# STM32F767IGT6.net
KiCad netlist of a schematic drawn in Altium Designer
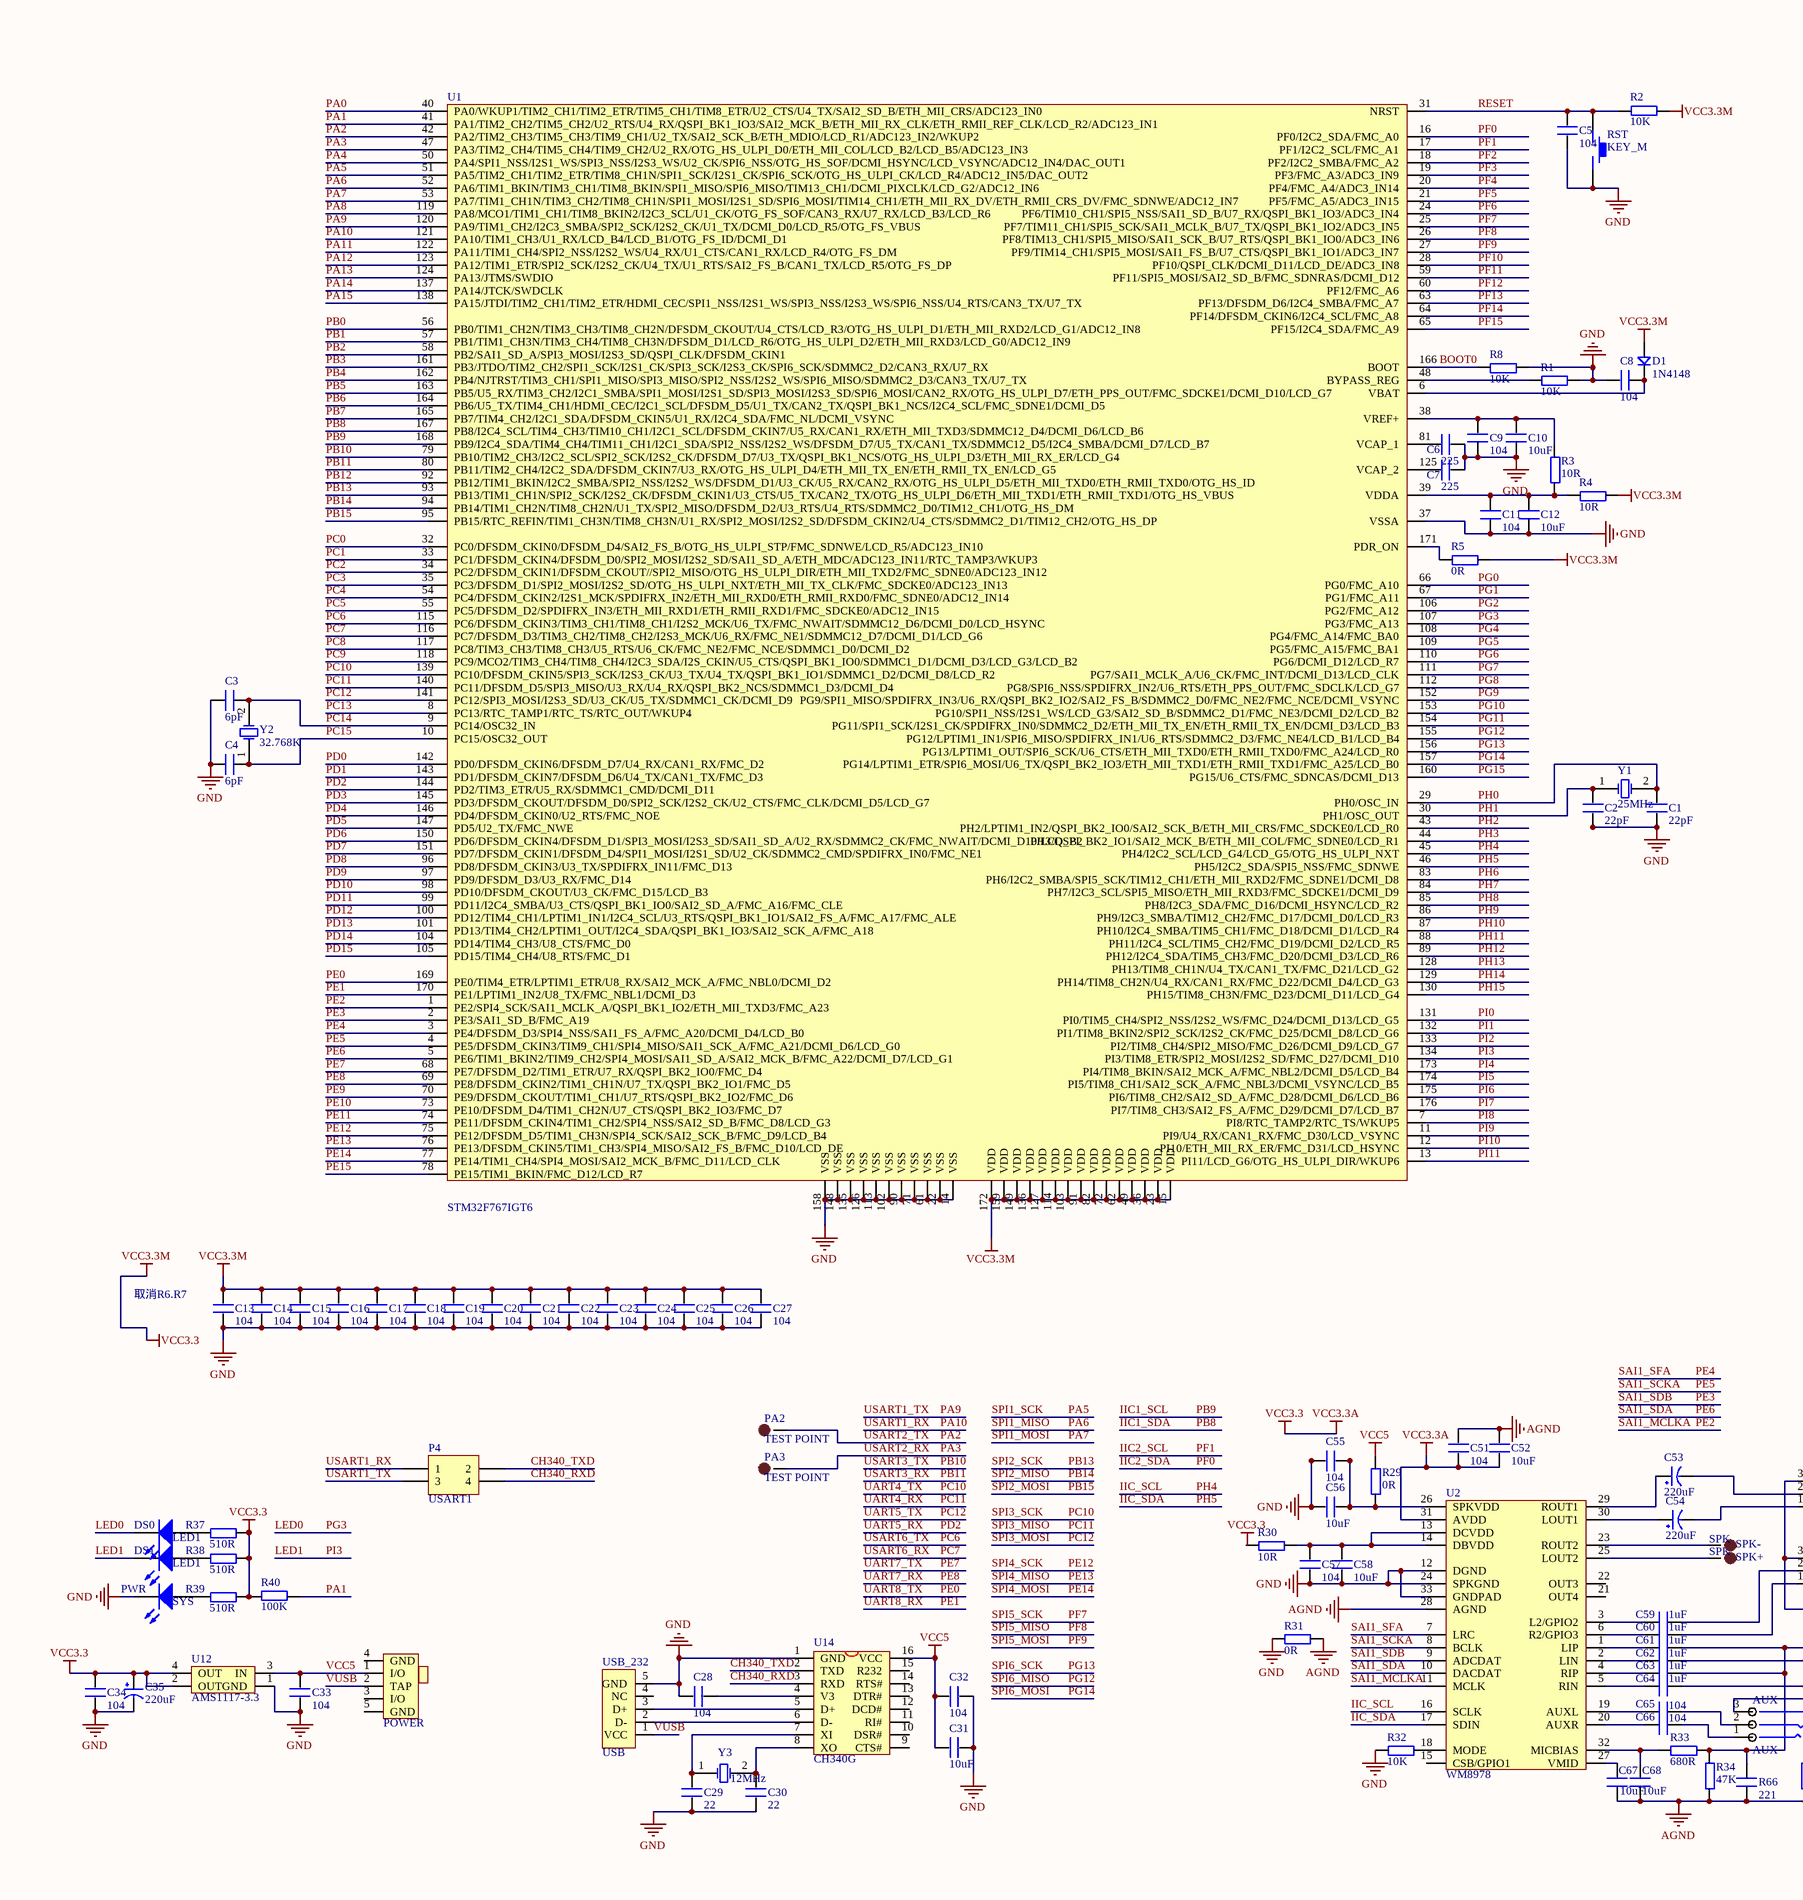
[diagram p0: STM32F767IGT6.SchDoc, left]
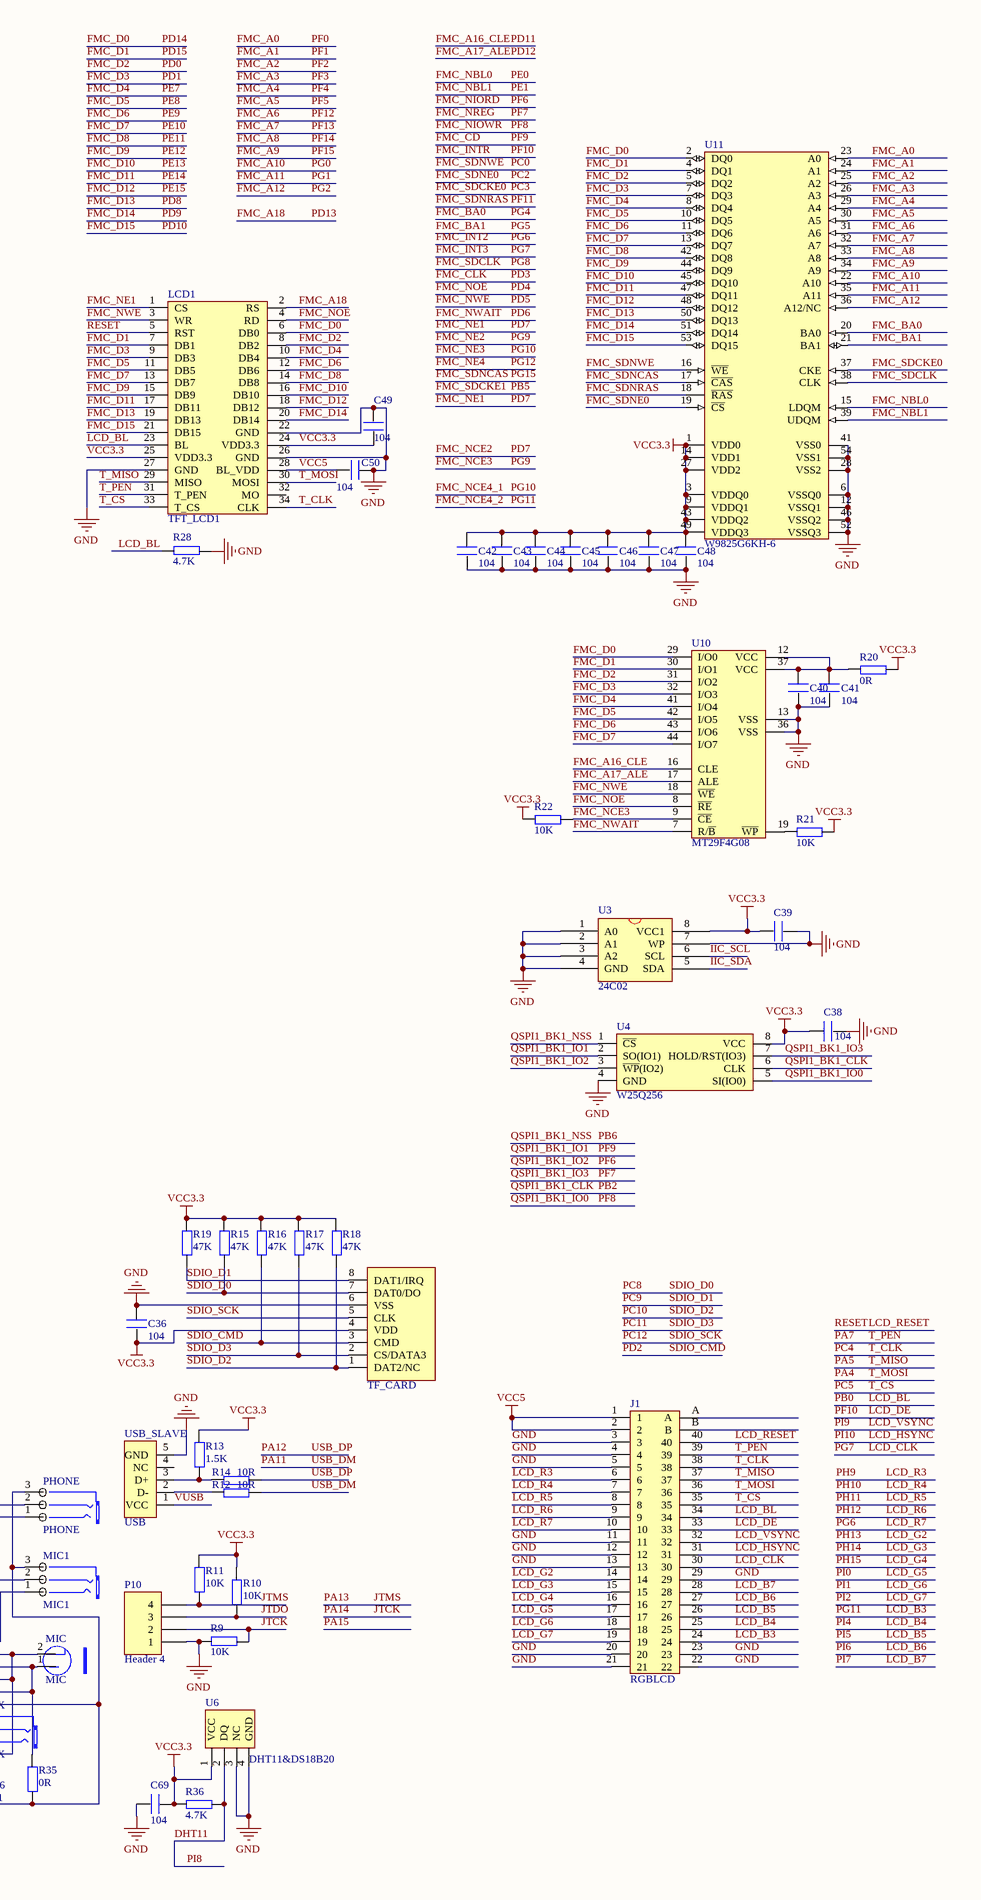
[diagram p1: STM32F767IGT6.SchDoc, right]

(export (version "E")
  (design (tool "Eeschema 10.0.6"))
  (components
    (comp (ref "AUX")
      (value "AUX")
      (footprint "PHONE_ST")
      (libsource (lib "阿波罗STM32F4&F7&H7底板封装库") (part "PHONE_M"))
    )
    (comp (ref "C1")
      (value "22pF")
      (footprint "C 0603_M")
      (libsource (lib "WarShip V3 STM32103封装库") (part "C"))
    )
    (comp (ref "C2")
      (value "22pF")
      (footprint "C 0603_M")
      (libsource (lib "WarShip V3 STM32103封装库") (part "C"))
    )
    (comp (ref "C3")
      (value "6pF")
      (footprint "C 0603_M")
      (libsource (lib "WarShip V3 STM32103封装库") (part "C"))
    )
    (comp (ref "C4")
      (value "6pF")
      (footprint "C 0603_M")
      (libsource (lib "WarShip V3 STM32103封装库") (part "C"))
    )
    (comp (ref "C5")
      (value "104")
      (footprint "C 0603_M")
      (libsource (lib "WarShip V3 STM32103封装库") (part "C"))
    )
    (comp (ref "C6") (value "225") (footprint "C 0603_M") (libsource (lib "阿波罗STM32F4&F7底板封装库") (part "C")))
    (comp (ref "C7") (value "225") (footprint "C 0603_M") (libsource (lib "阿波罗STM32F4&F7底板封装库") (part "C")))
    (comp (ref "C8") (value "104") (footprint "C 0603_M") (libsource (lib "阿波罗STM32F4&F7底板封装库") (part "C")))
    (comp (ref "C9") (value "104") (footprint "C 0603_M") (libsource (lib "阿波罗STM32F4&F7底板封装库") (part "C")))
    (comp (ref "C10") (value "10uF") (footprint "C 0603_M") (libsource (lib "阿波罗STM32F4&F7底板封装库") (part "C")))
    (comp (ref "C11") (value "104") (footprint "C 0603_M") (libsource (lib "阿波罗STM32F4&F7底板封装库") (part "C")))
    (comp (ref "C12") (value "10uF") (footprint "C 0603_M") (libsource (lib "阿波罗STM32F4&F7底板封装库") (part "C")))
    (comp (ref "C13") (value "104") (footprint "C 0603_M") (libsource (lib "STM32F429核心板封装库") (part "C")))
    (comp (ref "C14") (value "104") (footprint "C 0603_M") (libsource (lib "STM32F429核心板封装库") (part "C")))
    (comp (ref "C15") (value "104") (footprint "C 0603_M") (libsource (lib "STM32F429核心板封装库") (part "C")))
    (comp (ref "C16") (value "104") (footprint "C 0603_M") (libsource (lib "STM32F429核心板封装库") (part "C")))
    (comp (ref "C17") (value "104") (footprint "C 0603_M") (libsource (lib "STM32F429核心板封装库") (part "C")))
    (comp (ref "C18") (value "104") (footprint "C 0603_M") (libsource (lib "STM32F429核心板封装库") (part "C")))
    (comp (ref "C19") (value "104") (footprint "C 0603_M") (libsource (lib "STM32F429核心板封装库") (part "C")))
    (comp (ref "C20") (value "104") (footprint "C 0603_M") (libsource (lib "STM32F429核心板封装库") (part "C")))
    (comp (ref "C21") (value "104") (footprint "C 0603_M") (libsource (lib "STM32F429核心板封装库") (part "C")))
    (comp (ref "C22") (value "104") (footprint "C 0603_M") (libsource (lib "STM32F429核心板封装库") (part "C")))
    (comp (ref "C23") (value "104") (footprint "C 0603_M") (libsource (lib "STM32F429核心板封装库") (part "C")))
    (comp (ref "C24") (value "104") (footprint "C 0603_M") (libsource (lib "STM32F429核心板封装库") (part "C")))
    (comp (ref "C25") (value "104") (footprint "C 0603_M") (libsource (lib "STM32F429核心板封装库") (part "C")))
    (comp (ref "C26") (value "104") (footprint "C 0603_M") (libsource (lib "STM32F429核心板封装库") (part "C")))
    (comp (ref "C27") (value "104") (footprint "C 0603_M") (libsource (lib "STM32F429核心板封装库") (part "C")))
    (comp (ref "C28")
      (value "104")
      (footprint "C 0603_M")
      (libsource (lib "WarShip V3 STM32103封装库") (part "C"))
    )
    (comp (ref "C29")
      (value "22")
      (footprint "C 0603_M")
      (libsource (lib "WarShip V3 STM32103封装库") (part "C"))
    )
    (comp (ref "C30")
      (value "22")
      (footprint "C 0603_M")
      (libsource (lib "WarShip V3 STM32103封装库") (part "C"))
    )
    (comp (ref "C31")
      (value "10uF")
      (footprint "C 0603_M")
      (libsource (lib "WarShip V3 STM32103封装库") (part "C"))
    )
    (comp (ref "C32")
      (value "104")
      (footprint "C 0603_M")
      (libsource (lib "WarShip V3 STM32103封装库") (part "C"))
    )
    (comp (ref "C33")
      (value "104")
      (footprint "C 0603_M")
      (libsource (lib "WarShip V3 STM32103封装库") (part "C"))
    )
    (comp (ref "C34")
      (value "104")
      (footprint "C 0603_M")
      (libsource (lib "WarShip V3 STM32103封装库") (part "C"))
    )
    (comp (ref "C35")
      (value "220uF")
      (footprint "CT 6*6 - C")
      (libsource (lib "WarShip V3 STM32103封装库") (part "CAP"))
    )
    (comp (ref "C36")
      (value "104")
      (footprint "C 0603_M")
      (libsource (lib "WarShip V3 STM32103封装库") (part "C"))
    )
    (comp (ref "C38")
      (value "104")
      (footprint "C 0603_M")
      (libsource (lib "WarShip V3 STM32103封装库") (part "C"))
    )
    (comp (ref "C39")
      (value "104")
      (footprint "C 0603_M")
      (libsource (lib "WarShip V3 STM32103封装库") (part "C"))
    )
    (comp (ref "C40")
      (value "104")
      (footprint "C 0603_M")
      (libsource (lib "WarShip V3 STM32103封装库") (part "C"))
    )
    (comp (ref "C41")
      (value "104")
      (footprint "C 0603_M")
      (libsource (lib "WarShip V3 STM32103封装库") (part "C"))
    )
    (comp (ref "C42")
      (value "104")
      (footprint "C 0603_M")
      (libsource (lib "WarShip V3 STM32103封装库") (part "C"))
    )
    (comp (ref "C43")
      (value "104")
      (footprint "C 0603_M")
      (libsource (lib "WarShip V3 STM32103封装库") (part "C"))
    )
    (comp (ref "C44")
      (value "104")
      (footprint "C 0603_M")
      (libsource (lib "WarShip V3 STM32103封装库") (part "C"))
    )
    (comp (ref "C45")
      (value "104")
      (footprint "C 0603_M")
      (libsource (lib "WarShip V3 STM32103封装库") (part "C"))
    )
    (comp (ref "C46")
      (value "104")
      (footprint "C 0603_M")
      (libsource (lib "WarShip V3 STM32103封装库") (part "C"))
    )
    (comp (ref "C47")
      (value "104")
      (footprint "C 0603_M")
      (libsource (lib "WarShip V3 STM32103封装库") (part "C"))
    )
    (comp (ref "C48")
      (value "104")
      (footprint "C 0603_M")
      (libsource (lib "WarShip V3 STM32103封装库") (part "C"))
    )
    (comp (ref "C49") (value "104") (footprint "C 0603_M") (libsource (lib "MYCOMLIB") (part "C")))
    (comp (ref "C50") (value "104") (footprint "C 0603_M") (libsource (lib "MYCOMLIB") (part "C")))
    (comp (ref "C51") (value "104") (footprint "C 0603_M") (libsource (lib "阿波罗STM32F4&F7底板封装库") (part "C")))
    (comp (ref "C52") (value "10uF") (footprint "C 0603_M") (libsource (lib "阿波罗STM32F4&F7底板封装库") (part "C")))
    (comp (ref "C53")
      (value "220uF")
      (footprint "cc4*5.4")
      (libsource (lib "阿波罗STM32F4&F7底板封装库") (part "CAP"))
    )
    (comp (ref "C54")
      (value "220uF")
      (footprint "cc4*5.4")
      (libsource (lib "阿波罗STM32F4&F7底板封装库") (part "CAP"))
    )
    (comp (ref "C55") (value "104") (footprint "C 0603_M") (libsource (lib "阿波罗STM32F4&F7底板封装库") (part "C")))
    (comp (ref "C56") (value "10uF") (footprint "C 0603_M") (libsource (lib "阿波罗STM32F4&F7底板封装库") (part "C")))
    (comp (ref "C57") (value "104") (footprint "C 0603_M") (libsource (lib "阿波罗STM32F4&F7底板封装库") (part "C")))
    (comp (ref "C58") (value "10uF") (footprint "C 0603_M") (libsource (lib "阿波罗STM32F4&F7底板封装库") (part "C")))
    (comp (ref "C59") (value "1uF") (footprint "C 0603_M") (libsource (lib "阿波罗STM32F4&F7底板封装库") (part "C")))
    (comp (ref "C60") (value "1uF") (footprint "C 0603_M") (libsource (lib "阿波罗STM32F4&F7底板封装库") (part "C")))
    (comp (ref "C61") (value "1uF") (footprint "C 0603_M") (libsource (lib "阿波罗STM32F4&F7底板封装库") (part "C")))
    (comp (ref "C62") (value "1uF") (footprint "C 0603_M") (libsource (lib "阿波罗STM32F4&F7底板封装库") (part "C")))
    (comp (ref "C63") (value "1uF") (footprint "C 0603_M") (libsource (lib "阿波罗STM32F4&F7底板封装库") (part "C")))
    (comp (ref "C64") (value "1uF") (footprint "C 0603_M") (libsource (lib "阿波罗STM32F4&F7底板封装库") (part "C")))
    (comp (ref "C65") (value "104") (footprint "C 0603_M") (libsource (lib "阿波罗STM32F4&F7底板封装库") (part "C")))
    (comp (ref "C66") (value "104") (footprint "C 0603_M") (libsource (lib "阿波罗STM32F4&F7底板封装库") (part "C")))
    (comp (ref "C67") (value "10uF") (footprint "C 0603_M") (libsource (lib "阿波罗STM32F4&F7底板封装库") (part "C")))
    (comp (ref "C68") (value "10uF") (footprint "C 0603_M") (libsource (lib "阿波罗STM32F4&F7底板封装库") (part "C")))
    (comp (ref "C69")
      (value "104")
      (footprint "C 0603_M")
      (libsource (lib "WarShip V3 STM32103封装库") (part "C"))
    )
    (comp (ref "D1")
      (value "1N4148")
      (footprint "DIODE_SOP")
      (libsource (lib "WarShip V3 STM32103封装库") (part "D"))
    )
    (comp (ref "DS0")
      (value "LED1")
      (footprint "SMDLED")
      (description "Typical RED, GREEN, YELLOW, AMBER GaAs LED")
      (fields (field (name "PUBLISHER") "Altium Limited"))
      (libsource (lib "Miscellaneous Devices") (part "LED2"))
    )
    (comp (ref "DS1")
      (value "LED1")
      (footprint "SMDLED")
      (description "Typical RED, GREEN, YELLOW, AMBER GaAs LED")
      (fields (field (name "PUBLISHER") "Altium Limited"))
      (libsource (lib "Miscellaneous Devices") (part "LED2"))
    )
    (comp (ref "J1")
      (value "RGBLCD")
      (footprint "FPC-TOP40")
      (description "FPC-40P-0.5mm")
      (libsource (lib "STM32F429核心板封装库") (part "FPC-40"))
    )
    (comp (ref "LCD1")
      (value "TFT_LCD1")
      (footprint "DB2*17-3.5")
      (libsource (lib "3.5TFTLCD封装库") (part "TFT_LCD2"))
    )
    (comp (ref "MIC")
      (value "MIC")
      (footprint "MIC-6022")
      (libsource (lib "阿波罗STM32F4&F7&H7底板封装库") (part "MIC"))
    )
    (comp (ref "MIC1")
      (value "MIC1")
      (footprint "PHONE_ST")
      (libsource (lib "阿波罗STM32F4&F7&H7底板封装库") (part "PHONE_M"))
    )
    (comp (ref "P4")
      (value "USART1")
      (footprint "HDR2.54-LI-2x2P")
      (description "Header, 2-Pin, Dual row")
      (fields (field (name "PUBLISHER") "Altium Limited"))
      (libsource (lib "WarShip V3 STM32103封装库") (part "Header 2X2"))
    )
    (comp (ref "P10")
      (value "Header 4")
      (footprint "HDR2.54-LI-4P")
      (description "Header, 4-Pin")
      (fields (field (name "PUBLISHER") "Altium Limited"))
      (libsource (lib "WarShip V3 STM32103封装库") (part "Header 4"))
    )
    (comp (ref "PA2")
      (value "TEST POINT")
      (footprint "TP-1.5")
      (description "测试点")
      (libsource (lib "STM32F429核心板封装库") (part "TEST-POINT"))
    )
    (comp (ref "PA3")
      (value "TEST POINT")
      (footprint "TP-1.5")
      (description "测试点")
      (libsource (lib "STM32F429核心板封装库") (part "TEST-POINT"))
    )
    (comp (ref "PHONE")
      (value "PHONE")
      (footprint "PHONE_ST")
      (libsource (lib "阿波罗STM32F4&F7&H7底板封装库") (part "PHONE_M"))
    )
    (comp (ref "POWER")
      (value "BUTTON_DIP3")
      (footprint "BTN8.8*4.6")
      (description "拨动开关SS-12F44")
      (libsource (lib "Pandora_STM32L4_Board_V2.4") (part "BUTTON_DIP3"))
    )
    (comp (ref "PWR")
      (value "SYS")
      (footprint "SMDLED")
      (description "Typical RED, GREEN, YELLOW, AMBER GaAs LED")
      (fields (field (name "PUBLISHER") "Altium Limited"))
      (libsource (lib "Miscellaneous Devices") (part "LED2"))
    )
    (comp (ref "R1") (value "10K") (footprint "R 0603_M") (libsource (lib "阿波罗STM32F4&F7底板封装库") (part "R")))
    (comp (ref "R2")
      (value "10K")
      (footprint "R 0603_M")
      (libsource (lib "WarShip V3 STM32103封装库") (part "R"))
    )
    (comp (ref "R3") (value "10R") (footprint "R 0603_M") (libsource (lib "阿波罗STM32F4&F7底板封装库") (part "R")))
    (comp (ref "R4") (value "10R") (footprint "R 0603_M") (libsource (lib "阿波罗STM32F4&F7底板封装库") (part "R")))
    (comp (ref "R5") (value "0R") (footprint "R 0603_M") (libsource (lib "阿波罗STM32F4&F7底板封装库") (part "R")))
    (comp (ref "R8") (value "10K") (footprint "R 0603_M") (libsource (lib "阿波罗STM32F4&F7底板封装库") (part "R")))
    (comp (ref "R9")
      (value "10K")
      (footprint "R 0603_M")
      (libsource (lib "WarShip V3 STM32103封装库") (part "R"))
    )
    (comp (ref "R10")
      (value "10K")
      (footprint "R 0603_M")
      (libsource (lib "WarShip V3 STM32103封装库") (part "R"))
    )
    (comp (ref "R11")
      (value "10K")
      (footprint "R 0603_M")
      (libsource (lib "WarShip V3 STM32103封装库") (part "R"))
    )
    (comp (ref "R12")
      (value "10R")
      (footprint "R 0603_M")
      (libsource (lib "WarShip V3 STM32103封装库") (part "R"))
    )
    (comp (ref "R13")
      (value "1.5K")
      (footprint "R 0603_M")
      (libsource (lib "WarShip V3 STM32103封装库") (part "R"))
    )
    (comp (ref "R14")
      (value "10R")
      (footprint "R 0603_M")
      (libsource (lib "WarShip V3 STM32103封装库") (part "R"))
    )
    (comp (ref "R15")
      (value "47K")
      (footprint "R 0603_M")
      (libsource (lib "WarShip V3 STM32103封装库") (part "R"))
    )
    (comp (ref "R16")
      (value "47K")
      (footprint "R 0603_M")
      (libsource (lib "WarShip V3 STM32103封装库") (part "R"))
    )
    (comp (ref "R17")
      (value "47K")
      (footprint "R 0603_M")
      (libsource (lib "WarShip V3 STM32103封装库") (part "R"))
    )
    (comp (ref "R18")
      (value "47K")
      (footprint "R 0603_M")
      (libsource (lib "WarShip V3 STM32103封装库") (part "R"))
    )
    (comp (ref "R19")
      (value "47K")
      (footprint "R 0603_M")
      (libsource (lib "WarShip V3 STM32103封装库") (part "R"))
    )
    (comp (ref "R20")
      (value "0R")
      (footprint "R 0603_M")
      (libsource (lib "WarShip V3 STM32103封装库") (part "R"))
    )
    (comp (ref "R21")
      (value "10K")
      (footprint "R 0603_M")
      (libsource (lib "WarShip V3 STM32103封装库") (part "R"))
    )
    (comp (ref "R22")
      (value "10K")
      (footprint "R 0603_M")
      (libsource (lib "WarShip V3 STM32103封装库") (part "R"))
    )
    (comp (ref "R28") (value "4.7K") (footprint "R 0603_M") (libsource (lib "MYCOMLIB") (part "R")))
    (comp (ref "R29") (value "0R") (footprint "R 0603_M") (libsource (lib "阿波罗STM32F4&F7底板封装库") (part "R")))
    (comp (ref "R30") (value "10R") (footprint "R 0603_M") (libsource (lib "阿波罗STM32F4&F7底板封装库") (part "R")))
    (comp (ref "R31") (value "0R") (footprint "R 0603_M") (libsource (lib "阿波罗STM32F4&F7底板封装库") (part "R")))
    (comp (ref "R32") (value "10K") (footprint "R 0603_M") (libsource (lib "阿波罗STM32F4&F7底板封装库") (part "R")))
    (comp (ref "R33") (value "680R") (footprint "R 0603_M") (libsource (lib "阿波罗STM32F4&F7底板封装库") (part "R")))
    (comp (ref "R34") (value "47K") (footprint "R 0603_M") (libsource (lib "阿波罗STM32F4&F7底板封装库") (part "R")))
    (comp (ref "R35") (value "0R") (footprint "R 0603_M") (libsource (lib "阿波罗STM32F4&F7底板封装库") (part "R")))
    (comp (ref "R36")
      (value "4.7K")
      (footprint "R 0603_M")
      (libsource (lib "WarShip V3 STM32103封装库") (part "R"))
    )
    (comp (ref "R37") (value "510R") (footprint "R 0603_M") (libsource (lib "MYCOMLIB") (part "R")))
    (comp (ref "R38") (value "510R") (footprint "R 0603_M") (libsource (lib "MYCOMLIB") (part "R")))
    (comp (ref "R39") (value "510R") (footprint "R 0603_M") (libsource (lib "MYCOMLIB") (part "R")))
    (comp (ref "R40") (value "100K") (footprint "R 0603_M") (libsource (lib "MYCOMLIB") (part "R")))
    (comp (ref "R66") (value "221") (footprint "C 0603_M") (libsource (lib "阿波罗STM32F4&F7底板封装库") (part "C")))
    (comp (ref "RST")
      (value "KEY_M")
      (footprint "TSW SMD-3*6*2.5")
      (libsource (lib "STM32F429核心板封装库") (part "KEY_M"))
    )
    (comp (ref "SPK+")
      (value "SPK")
      (footprint "TP-1.5")
      (description "测试点")
      (libsource (lib "STM32F429核心板封装库") (part "TEST-POINT"))
    )
    (comp (ref "SPK-")
      (value "SPK")
      (footprint "TP-1.5")
      (description "测试点")
      (libsource (lib "STM32F429核心板封装库") (part "TEST-POINT"))
    )
    (comp (ref "TF_CARD")
      (value "SD-MICRO-TF")
      (footprint "SD-MICRO-TF")
      (description "SD,MICRO,TF")
      (libsource (lib "Pandora_STM32L4_Board_V2.4") (part "SD-MICRO-TF"))
    )
    (comp (ref "U1")
      (value "STM32F767IGT6")
      (footprint "LQFP176")
      (libsource (lib "STM32F767核心板封装库") (part "STM32F767IGT6"))
    )
    (comp (ref "U2")
      (value "WM8978")
      (footprint "qfn32")
      (description "24bit ADC&DAC")
      (libsource (lib "STM32H743") (part "WM8978"))
    )
    (comp (ref "U3")
      (value "24C02")
      (footprint "SOP8_M")
      (libsource (lib "WarShip V3 STM32103封装库") (part "24C256"))
    )
    (comp (ref "U4")
      (value "W25Q256")
      (footprint "WSON8")
      (description "W25Q128")
      (libsource (lib "STM32F767核心板封装库") (part "W25Q128"))
    )
    (comp (ref "U6")
      (value "DHT11&DS18B20")
      (footprint "DHT11")
      (description "数字温湿度传感器")
      (libsource (lib "WarShip V3 STM32103封装库") (part "DHT11"))
    )
    (comp (ref "U10")
      (value "MT29F4G08")
      (footprint "TSOP48")
      (description "256MB NAND FLASH")
      (libsource (lib "STM32F429核心板封装库") (part "K9F2G08U0C"))
    )
    (comp (ref "U11")
      (value "W9825G6KH-6")
      (footprint "TSOP54")
      (description "32MB SDRAM")
      (libsource (lib "STM32F429核心板封装库") (part "IS42S16160B"))
    )
    (comp (ref "U12")
      (value "AMS1117-3.3")
      (footprint "AMS1117")
      (libsource (lib "WarShip V3 STM32103封装库") (part "AMS1117"))
    )
    (comp (ref "U14")
      (value "CH340G")
      (footprint "SOP16_M")
      (description "USB2UART")
      (libsource (lib "WarShip V3 STM32103封装库") (part "CH340G"))
    )
    (comp (ref "USB_232")
      (value "USB")
      (footprint "USB-MINI-A")
      (libsource (lib "WarShip V3 STM32103封装库") (part "USB5"))
    )
    (comp (ref "USB_SLAVE")
      (value "USB")
      (footprint "USB-MINI-A")
      (libsource (lib "WarShip V3 STM32103封装库") (part "USB5"))
    )
    (comp (ref "Y1")
      (value "25MHz")
      (footprint "OSC HC-49S")
      (description "Crystal Oscillator")
      (fields (field (name "PUBLISHER") "Altium Limited"))
      (libsource (lib "WarShip V3 STM32103封装库") (part "XTAL"))
    )
    (comp (ref "Y2")
      (value "32.768K")
      (footprint "OSC-2x6-WI-A")
      (description "Crystal Oscillator")
      (fields (field (name "PUBLISHER") "Altium Limited"))
      (libsource (lib "WarShip V3 STM32103封装库") (part "XTAL"))
    )
    (comp (ref "Y3")
      (value "12MHz")
      (footprint "OSC HC-49S")
      (description "Crystal Oscillator")
      (fields (field (name "PUBLISHER") "Altium Limited"))
      (libsource (lib "WarShip V3 STM32103封装库") (part "XTAL"))
    )
  )
  (nets
    (net (code "1") (name "/BOOT0") (class "Default")
      (node (ref "R8") (pin "1") (pintype "passive"))
      (node (ref "U1") (pin "166") (pinfunction "BOOT_166") (pintype "passive"))
    )
    (net (code "2") (name "/CH340_RXD") (class "Default")
      (node (ref "P4") (pin "4") (pinfunction "4_4") (pintype "passive"))
      (node (ref "U14") (pin "3") (pinfunction "RXD_3") (pintype "passive"))
    )
    (net (code "3") (name "/CH340_TXD") (class "Default")
      (node (ref "P4") (pin "2") (pinfunction "2_2") (pintype "passive"))
      (node (ref "U14") (pin "2") (pinfunction "TXD_2") (pintype "passive"))
    )
    (net (code "4") (name "/DHT11") (class "Default")
      (node (ref "R36") (pin "2") (pintype "passive"))
      (node (ref "U1") (pin "7") (pinfunction "PI8/RTC_TAMP2/RTC_TS/WKUP5_7") (pintype "passive"))
      (node (ref "U6") (pin "2") (pinfunction "DQ_2") (pintype "passive"))
    )
    (net (code "5") (name "/FMC_A0") (class "Default")
      (node (ref "U1") (pin "16") (pinfunction "PF0/I2C2_SDA/FMC_A0_16") (pintype "passive"))
      (node (ref "U11") (pin "23") (pinfunction "A0_23") (pintype "input"))
    )
    (net (code "6") (name "/FMC_A1") (class "Default")
      (node (ref "U1") (pin "17") (pinfunction "PF1/I2C2_SCL/FMC_A1_17") (pintype "passive"))
      (node (ref "U11") (pin "24") (pinfunction "A1_24") (pintype "input"))
    )
    (net (code "7") (name "/FMC_A2") (class "Default")
      (node (ref "U1") (pin "18") (pinfunction "PF2/I2C2_SMBA/FMC_A2_18") (pintype "passive"))
      (node (ref "U11") (pin "25") (pinfunction "A2_25") (pintype "input"))
    )
    (net (code "8") (name "/FMC_A3") (class "Default")
      (node (ref "U1") (pin "19") (pinfunction "PF3/FMC_A3/ADC3_IN9_19") (pintype "passive"))
      (node (ref "U11") (pin "26") (pinfunction "A3_26") (pintype "input"))
    )
    (net (code "9") (name "/FMC_A4") (class "Default")
      (node (ref "U1") (pin "20") (pinfunction "PF4/FMC_A4/ADC3_IN14_20") (pintype "passive"))
      (node (ref "U11") (pin "29") (pinfunction "A4_29") (pintype "input"))
    )
    (net (code "10") (name "/FMC_A5") (class "Default")
      (node (ref "U1") (pin "21") (pinfunction "PF5/FMC_A5/ADC3_IN15_21") (pintype "passive"))
      (node (ref "U11") (pin "30") (pinfunction "A5_30") (pintype "input"))
    )
    (net (code "11") (name "/FMC_A6") (class "Default")
      (node (ref "U1") (pin "60") (pinfunction "PF12/FMC_A6_60") (pintype "passive"))
      (node (ref "U11") (pin "31") (pinfunction "A6_31") (pintype "input"))
    )
    (net (code "12") (name "/FMC_A7") (class "Default")
      (node (ref "U1") (pin "63") (pinfunction "PF13/DFSDM_D6/I2C4_SMBA/FMC_A7_63") (pintype "passive"))
      (node (ref "U11") (pin "32") (pinfunction "A7_32") (pintype "input"))
    )
    (net (code "13") (name "/FMC_A8") (class "Default")
      (node (ref "U1") (pin "64") (pinfunction "PF14/DFSDM_CKIN6/I2C4_SCL/FMC_A8_64") (pintype "passive"))
      (node (ref "U11") (pin "33") (pinfunction "A8_33") (pintype "input"))
    )
    (net (code "14") (name "/FMC_A9") (class "Default")
      (node (ref "U1") (pin "65") (pinfunction "PF15/I2C4_SDA/FMC_A9_65") (pintype "passive"))
      (node (ref "U11") (pin "34") (pinfunction "A9_34") (pintype "input"))
    )
    (net (code "15") (name "/FMC_A10") (class "Default")
      (node (ref "U1") (pin "66") (pinfunction "PG0/FMC_A10_66") (pintype "passive"))
      (node (ref "U11") (pin "22") (pinfunction "A10_22") (pintype "input"))
    )
    (net (code "16") (name "/FMC_A11") (class "Default")
      (node (ref "U1") (pin "67") (pinfunction "PG1/FMC_A11_67") (pintype "passive"))
      (node (ref "U11") (pin "35") (pinfunction "A11_35") (pintype "input"))
    )
    (net (code "17") (name "/FMC_A12") (class "Default")
      (node (ref "U1") (pin "106") (pinfunction "PG2/FMC_A12_106") (pintype "passive"))
      (node (ref "U11") (pin "36") (pinfunction "A12/NC_36") (pintype "input"))
    )
    (net (code "18") (name "/FMC_A16_CLE") (class "Default")
      (node (ref "U1") (pin "99") (pinfunction "PD11/I2C4_SMBA/U3_CTS/QSPI_BK1_IO0/SAI2_SD_A/FMC_A16/FMC_CLE_99") (pintype "passive"))
      (node (ref "U10") (pin "16") (pinfunction "CLE_16") (pintype "passive"))
    )
    (net (code "19") (name "/FMC_A17_ALE") (class "Default")
      (node (ref "U1") (pin "100") (pinfunction "PD12/TIM4_CH1/LPTIM1_IN1/I2C4_SCL/U3_RTS/QSPI_BK1_IO1/SAI2_FS_A/FMC_A17/FMC_ALE_100") (pintype "passive"))
      (node (ref "U10") (pin "17") (pinfunction "ALE_17") (pintype "passive"))
    )
    (net (code "20") (name "/FMC_A18") (class "Default")
      (node (ref "LCD1") (pin "2") (pinfunction "RS_2") (pintype "passive"))
      (node (ref "U1") (pin "101") (pinfunction "PD13/TIM4_CH2/LPTIM1_OUT/I2C4_SDA/QSPI_BK1_IO3/SAI2_SCK_A/FMC_A18_101") (pintype "passive"))
    )
    (net (code "21") (name "/FMC_BA0") (class "Default")
      (node (ref "U1") (pin "108") (pinfunction "PG4/FMC_A14/FMC_BA0_108") (pintype "passive"))
      (node (ref "U11") (pin "20") (pinfunction "BA0_20") (pintype "input"))
    )
    (net (code "22") (name "/FMC_BA1") (class "Default")
      (node (ref "U1") (pin "109") (pinfunction "PG5/FMC_A15/FMC_BA1_109") (pintype "passive"))
      (node (ref "U11") (pin "21") (pinfunction "BA1_21") (pintype "bidirectional"))
    )
    (net (code "23") (name "/FMC_CD") (class "Default")
      (node (ref "U1") (pin "27") (pinfunction "PF9/TIM14_CH1/SPI5_MOSI/SAI1_FS_B/U7_CTS/QSPI_BK1_IO1/ADC3_IN7_27") (pintype "passive"))
      (node (ref "U4") (pin "2") (pinfunction "SO(IO1)_2") (pintype "passive"))
    )
    (net (code "24") (name "/FMC_CLK") (class "Default")
      (node (ref "U1") (pin "145") (pinfunction "PD3/DFSDM_CKOUT/DFSDM_D0/SPI2_SCK/I2S2_CK/U2_CTS/FMC_CLK/DCMI_D5/LCD_G7_145") (pintype "passive"))
    )
    (net (code "25") (name "/FMC_D0") (class "Default")
      (node (ref "LCD1") (pin "6") (pinfunction "DB0_6") (pintype "passive"))
      (node (ref "U1") (pin "104") (pinfunction "PD14/TIM4_CH3/U8_CTS/FMC_D0_104") (pintype "passive"))
      (node (ref "U10") (pin "29") (pinfunction "I/O0_29") (pintype "passive"))
      (node (ref "U11") (pin "2") (pinfunction "DQ0_2") (pintype "bidirectional"))
    )
    (net (code "26") (name "/FMC_D1") (class "Default")
      (node (ref "LCD1") (pin "7") (pinfunction "DB1_7") (pintype "passive"))
      (node (ref "U1") (pin "105") (pinfunction "PD15/TIM4_CH4/U8_RTS/FMC_D1_105") (pintype "passive"))
      (node (ref "U10") (pin "30") (pinfunction "I/O1_30") (pintype "passive"))
      (node (ref "U11") (pin "4") (pinfunction "DQ1_4") (pintype "bidirectional"))
    )
    (net (code "27") (name "/FMC_D2") (class "Default")
      (node (ref "LCD1") (pin "8") (pinfunction "DB2_8") (pintype "passive"))
      (node (ref "U1") (pin "142") (pinfunction "PD0/DFSDM_CKIN6/DFSDM_D7/U4_RX/CAN1_RX/FMC_D2_142") (pintype "passive"))
      (node (ref "U10") (pin "31") (pinfunction "I/O2_31") (pintype "passive"))
      (node (ref "U11") (pin "5") (pinfunction "DQ2_5") (pintype "bidirectional"))
    )
    (net (code "28") (name "/FMC_D3") (class "Default")
      (node (ref "LCD1") (pin "9") (pinfunction "DB3_9") (pintype "passive"))
      (node (ref "U1") (pin "143") (pinfunction "PD1/DFSDM_CKIN7/DFSDM_D6/U4_TX/CAN1_TX/FMC_D3_143") (pintype "passive"))
      (node (ref "U10") (pin "32") (pinfunction "I/O3_32") (pintype "passive"))
      (node (ref "U11") (pin "7") (pinfunction "DQ3_7") (pintype "bidirectional"))
    )
    (net (code "29") (name "/FMC_D4") (class "Default")
      (node (ref "LCD1") (pin "10") (pinfunction "DB4_10") (pintype "passive"))
      (node (ref "U1") (pin "68") (pinfunction "PE7/DFSDM_D2/TIM1_ETR/U7_RX/QSPI_BK2_IO0/FMC_D4_68") (pintype "passive"))
      (node (ref "U10") (pin "41") (pinfunction "I/O4_41") (pintype "passive"))
      (node (ref "U11") (pin "8") (pinfunction "DQ4_8") (pintype "bidirectional"))
    )
    (net (code "30") (name "/FMC_D5") (class "Default")
      (node (ref "LCD1") (pin "11") (pinfunction "DB5_11") (pintype "passive"))
      (node (ref "U1") (pin "69") (pinfunction "PE8/DFSDM_CKIN2/TIM1_CH1N/U7_TX/QSPI_BK2_IO1/FMC_D5_69") (pintype "passive"))
      (node (ref "U10") (pin "42") (pinfunction "I/O5_42") (pintype "passive"))
      (node (ref "U11") (pin "10") (pinfunction "DQ5_10") (pintype "bidirectional"))
    )
    (net (code "31") (name "/FMC_D6") (class "Default")
      (node (ref "LCD1") (pin "12") (pinfunction "DB6_12") (pintype "passive"))
      (node (ref "U1") (pin "70") (pinfunction "PE9/DFSDM_CKOUT/TIM1_CH1/U7_RTS/QSPI_BK2_IO2/FMC_D6_70") (pintype "passive"))
      (node (ref "U10") (pin "43") (pinfunction "I/O6_43") (pintype "passive"))
      (node (ref "U11") (pin "11") (pinfunction "DQ6_11") (pintype "bidirectional"))
    )
    (net (code "32") (name "/FMC_D7") (class "Default")
      (node (ref "LCD1") (pin "13") (pinfunction "DB7_13") (pintype "passive"))
      (node (ref "U1") (pin "73") (pinfunction "PE10/DFSDM_D4/TIM1_CH2N/U7_CTS/QSPI_BK2_IO3/FMC_D7_73") (pintype "passive"))
      (node (ref "U10") (pin "44") (pinfunction "I/O7_44") (pintype "passive"))
      (node (ref "U11") (pin "13") (pinfunction "DQ7_13") (pintype "bidirectional"))
    )
    (net (code "33") (name "/FMC_D8") (class "Default")
      (node (ref "LCD1") (pin "14") (pinfunction "DB8_14") (pintype "passive"))
      (node (ref "U1") (pin "74") (pinfunction "PE11/DFSDM_CKIN4/TIM1_CH2/SPI4_NSS/SAI2_SD_B/FMC_D8/LCD_G3_74") (pintype "passive"))
      (node (ref "U11") (pin "42") (pinfunction "DQ8_42") (pintype "bidirectional"))
    )
    (net (code "34") (name "/FMC_D9") (class "Default")
      (node (ref "LCD1") (pin "15") (pinfunction "DB9_15") (pintype "passive"))
      (node (ref "U1") (pin "75") (pinfunction "PE12/DFSDM_D5/TIM1_CH3N/SPI4_SCK/SAI2_SCK_B/FMC_D9/LCD_B4_75") (pintype "passive"))
      (node (ref "U11") (pin "44") (pinfunction "DQ9_44") (pintype "bidirectional"))
    )
    (net (code "35") (name "/FMC_D10") (class "Default")
      (node (ref "LCD1") (pin "16") (pinfunction "DB10_16") (pintype "passive"))
      (node (ref "U1") (pin "76") (pinfunction "PE13/DFSDM_CKIN5/TIM1_CH3/SPI4_MISO/SAI2_FS_B/FMC_D10/LCD_DE_76") (pintype "passive"))
      (node (ref "U11") (pin "45") (pinfunction "DQ10_45") (pintype "bidirectional"))
    )
    (net (code "36") (name "/FMC_D11") (class "Default")
      (node (ref "LCD1") (pin "17") (pinfunction "DB11_17") (pintype "passive"))
      (node (ref "U1") (pin "77") (pinfunction "PE14/TIM1_CH4/SPI4_MOSI/SAI2_MCK_B/FMC_D11/LCD_CLK_77") (pintype "passive"))
      (node (ref "U11") (pin "47") (pinfunction "DQ11_47") (pintype "bidirectional"))
    )
    (net (code "37") (name "/FMC_D12") (class "Default")
      (node (ref "LCD1") (pin "18") (pinfunction "DB12_18") (pintype "passive"))
      (node (ref "U1") (pin "78") (pinfunction "PE15/TIM1_BKIN/FMC_D12/LCD_R7_78") (pintype "passive"))
      (node (ref "U11") (pin "48") (pinfunction "DQ12_48") (pintype "bidirectional"))
    )
    (net (code "38") (name "/FMC_D13") (class "Default")
      (node (ref "LCD1") (pin "19") (pinfunction "DB13_19") (pintype "passive"))
      (node (ref "U1") (pin "96") (pinfunction "PD8/DFSDM_CKIN3/U3_TX/SPDIFRX_IN11/FMC_D13_96") (pintype "passive"))
      (node (ref "U11") (pin "50") (pinfunction "DQ13_50") (pintype "bidirectional"))
    )
    (net (code "39") (name "/FMC_D14") (class "Default")
      (node (ref "LCD1") (pin "20") (pinfunction "DB14_20") (pintype "passive"))
      (node (ref "U1") (pin "97") (pinfunction "PD9/DFSDM_D3/U3_RX/FMC_D14_97") (pintype "passive"))
      (node (ref "U11") (pin "51") (pinfunction "DQ14_51") (pintype "bidirectional"))
    )
    (net (code "40") (name "/FMC_D15") (class "Default")
      (node (ref "LCD1") (pin "21") (pinfunction "DB15_21") (pintype "passive"))
      (node (ref "U1") (pin "98") (pinfunction "PD10/DFSDM_CKOUT/U3_CK/FMC_D15/LCD_B3_98") (pintype "passive"))
      (node (ref "U11") (pin "53") (pinfunction "DQ15_53") (pintype "bidirectional"))
    )
    (net (code "41") (name "/FMC_INT2") (class "Default")
      (node (ref "J1") (pin "10") (pinfunction "10_10") (pintype "passive"))
      (node (ref "U1") (pin "110") (pinfunction "PG6/DCMI_D12/LCD_R7_110") (pintype "passive"))
    )
    (net (code "42") (name "/FMC_INT3") (class "Default")
      (node (ref "J1") (pin "30") (pinfunction "30_30") (pintype "passive"))
      (node (ref "U1") (pin "111") (pinfunction "PG7/SAI1_MCLK_A/U6_CK/FMC_INT/DCMI_D13/LCD_CLK_111") (pintype "passive"))
    )
    (net (code "43") (name "/FMC_INTR") (class "Default")
      (node (ref "J1") (pin "33") (pinfunction "33_33") (pintype "passive"))
      (node (ref "U1") (pin "28") (pinfunction "PF10/QSPI_CLK/DCMI_D11/LCD_DE/ADC3_IN8_28") (pintype "passive"))
    )
    (net (code "44") (name "/FMC_NBL0") (class "Default")
      (node (ref "U1") (pin "169") (pinfunction "PE0/TIM4_ETR/LPTIM1_ETR/U8_RX/SAI2_MCK_A/FMC_NBL0/DCMI_D2_169") (pintype "passive"))
      (node (ref "U11") (pin "15") (pinfunction "LDQM_15") (pintype "input"))
    )
    (net (code "45") (name "/FMC_NBL1") (class "Default")
      (node (ref "U1") (pin "170") (pinfunction "PE1/LPTIM1_IN2/U8_TX/FMC_NBL1/DCMI_D3_170") (pintype "passive"))
      (node (ref "U11") (pin "39") (pinfunction "UDQM_39") (pintype "input"))
    )
    (net (code "46") (name "/FMC_NCE2") (class "Default")
      (node (ref "LCD1") (pin "1") (pinfunction "CS_1") (pintype "passive"))
      (node (ref "U1") (pin "151") (pinfunction "PD7/DFSDM_CKIN1/DFSDM_D4/SPI1_MOSI/I2S1_SD/U2_CK/SDMMC2_CMD/SPDIFRX_IN0/FMC_NE1_151") (pintype "passive"))
    )
    (net (code "47") (name "/FMC_NCE3") (class "Default")
      (node (ref "R22") (pin "2") (pintype "passive"))
      (node (ref "U1") (pin "152") (pinfunction "PG9/SPI1_MISO/SPDIFRX_IN3/U6_RX/QSPI_BK2_IO2/SAI2_FS_B/SDMMC2_D0/FMC_NE2/FMC_NCE/DCMI_VSYNC_152") (pintype "passive"))
      (node (ref "U10") (pin "9") (pinfunction "~{CE}_9") (pintype "passive"))
    )
    (net (code "48") (name "/FMC_NCE4_1") (class "Default")
      (node (ref "U1") (pin "153") (pinfunction "PG10/SPI1_NSS/I2S1_WS/LCD_G3/SAI2_SD_B/SDMMC2_D1/FMC_NE3/DCMI_D2/LCD_B2_153") (pintype "passive"))
    )
    (net (code "49") (name "/FMC_NCE4_2") (class "Default")
      (node (ref "J1") (pin "24") (pinfunction "24_24") (pintype "passive"))
      (node (ref "U1") (pin "154") (pinfunction "PG11/SPI1_SCK/I2S1_CK/SPDIFRX_IN0/SDMMC2_D2/ETH_MII_TX_EN/ETH_RMII_TX_EN/DCMI_D3/LCD_B3_154") (pintype "passive"))
    )
    (net (code "50") (name "/FMC_NE4") (class "Default")
      (node (ref "U1") (pin "155") (pinfunction "PG12/LPTIM1_IN1/SPI6_MISO/SPDIFRX_IN1/U6_RTS/SDMMC2_D3/FMC_NE4/LCD_B1/LCD_B4_155") (pintype "passive"))
    )
    (net (code "51") (name "/FMC_NIORD") (class "Default")
      (node (ref "U1") (pin "24") (pinfunction "PF6/TIM10_CH1/SPI5_NSS/SAI1_SD_B/U7_RX/QSPI_BK1_IO3/ADC3_IN4_24") (pintype "passive"))
      (node (ref "U4") (pin "3") (pinfunction "~{WP}(IO2)_3") (pintype "passive"))
    )
    (net (code "52") (name "/FMC_NIOWR") (class "Default")
      (node (ref "U1") (pin "26") (pinfunction "PF8/TIM13_CH1/SPI5_MISO/SAI1_SCK_B/U7_RTS/QSPI_BK1_IO0/ADC3_IN6_26") (pintype "passive"))
      (node (ref "U4") (pin "5") (pinfunction "SI(IO0)_5") (pintype "power_in"))
    )
    (net (code "53") (name "/FMC_NOE") (class "Default")
      (node (ref "LCD1") (pin "4") (pinfunction "RD_4") (pintype "passive"))
      (node (ref "U1") (pin "146") (pinfunction "PD4/DFSDM_CKIN0/U2_RTS/FMC_NOE_146") (pintype "passive"))
      (node (ref "U10") (pin "8") (pinfunction "~{RE}_8") (pintype "passive"))
    )
    (net (code "54") (name "/FMC_NREG") (class "Default")
      (node (ref "U1") (pin "25") (pinfunction "PF7/TIM11_CH1/SPI5_SCK/SAI1_MCLK_B/U7_TX/QSPI_BK1_IO2/ADC3_IN5_25") (pintype "passive"))
      (node (ref "U4") (pin "7") (pinfunction "HOLD/RST(IO3)_7") (pintype "power_in"))
    )
    (net (code "55") (name "/FMC_NWAIT") (class "Default")
      (node (ref "U1") (pin "150") (pinfunction "PD6/DFSDM_CKIN4/DFSDM_D1/SPI3_MOSI/I2S3_SD/SAI1_SD_A/U2_RX/SDMMC2_CK/FMC_NWAIT/DCMI_D10/LCD_B2_150") (pintype "passive"))
      (node (ref "U10") (pin "7") (pinfunction "R/~{B}_7") (pintype "passive"))
    )
    (net (code "56") (name "/FMC_NWE") (class "Default")
      (node (ref "LCD1") (pin "3") (pinfunction "WR_3") (pintype "passive"))
      (node (ref "U1") (pin "147") (pinfunction "PD5/U2_TX/FMC_NWE_147") (pintype "passive"))
      (node (ref "U10") (pin "18") (pinfunction "~{WE}_18") (pintype "passive"))
    )
    (net (code "57") (name "/FMC_SDCKE0") (class "Default")
      (node (ref "U1") (pin "35") (pinfunction "PC3/DFSDM_D1/SPI2_MOSI/I2S2_SD/OTG_HS_ULPI_NXT/ETH_MII_TX_CLK/FMC_SDCKE0/ADC123_IN13_35") (pintype "passive"))
      (node (ref "U11") (pin "37") (pinfunction "CKE_37") (pintype "input"))
    )
    (net (code "58") (name "/FMC_SDCKE1") (class "Default")
      (node (ref "U1") (pin "163") (pinfunction "PB5/U5_RX/TIM3_CH2/I2C1_SMBA/SPI1_MOSI/I2S1_SD/SPI3_MOSI/I2S3_SD/SPI6_MOSI/CAN2_RX/OTG_HS_ULPI_D7/ETH_PPS_OUT/FMC_SDCKE1/DCMI_D10/LCD_G7_163") (pintype "passive"))
    )
    (net (code "59") (name "/FMC_SDCLK") (class "Default")
      (node (ref "U1") (pin "112") (pinfunction "PG8/SPI6_NSS/SPDIFRX_IN2/U6_RTS/ETH_PPS_OUT/FMC_SDCLK/LCD_G7_112") (pintype "passive"))
      (node (ref "U11") (pin "38") (pinfunction "CLK_38") (pintype "input"))
    )
    (net (code "60") (name "/FMC_SDNCAS") (class "Default")
      (node (ref "U1") (pin "160") (pinfunction "PG15/U6_CTS/FMC_SDNCAS/DCMI_D13_160") (pintype "passive"))
      (node (ref "U11") (pin "17") (pinfunction "~{CAS}_17") (pintype "input"))
    )
    (net (code "61") (name "/FMC_SDNE0") (class "Default")
      (node (ref "U1") (pin "34") (pinfunction "PC2/DFSDM_CKIN1/DFSDM_CKOUT//SPI2_MISO/OTG_HS_ULPI_DIR/ETH_MII_TXD2/FMC_SDNE0/ADC123_IN12_34") (pintype "passive"))
      (node (ref "U11") (pin "19") (pinfunction "~{CS}_19") (pintype "input"))
    )
    (net (code "62") (name "/FMC_SDNRAS") (class "Default")
      (node (ref "U1") (pin "59") (pinfunction "PF11/SPI5_MOSI/SAI2_SD_B/FMC_SDNRAS/DCMI_D12_59") (pintype "passive"))
      (node (ref "U11") (pin "18") (pinfunction "~{RAS}_18") (pintype "passive"))
    )
    (net (code "63") (name "/FMC_SDNWE") (class "Default")
      (node (ref "U1") (pin "32") (pinfunction "PC0/DFSDM_CKIN0/DFSDM_D4/SAI2_FS_B/OTG_HS_ULPI_STP/FMC_SDNWE/LCD_R5/ADC123_IN10_32") (pintype "passive"))
      (node (ref "U11") (pin "16") (pinfunction "~{WE}_16") (pintype "input"))
    )
    (net (code "64") (name "/IIC1_SCL") (class "Default")
      (node (ref "U1") (pin "168") (pinfunction "PB9/I2C4_SDA/TIM4_CH4/TIM11_CH1/I2C1_SDA/SPI2_NSS/I2S2_WS/DFSDM_D7/U5_TX/CAN1_TX/SDMMC12_D5/I2C4_SMBA/DCMI_D7/LCD_B7_168") (pintype "passive"))
    )
    (net (code "65") (name "/IIC1_SDA") (class "Default")
      (node (ref "U1") (pin "167") (pinfunction "PB8/I2C4_SCL/TIM4_CH3/TIM10_CH1/I2C1_SCL/DFSDM_CKIN7/U5_RX/CAN1_RX/ETH_MII_TXD3/SDMMC12_D4/DCMI_D6/LCD_B6_167") (pintype "passive"))
    )
    (net (code "66") (name "/IIC_SCL") (class "Default")
      (node (ref "U1") (pin "45") (pinfunction "PH4/I2C2_SCL/LCD_G4/LCD_G5/OTG_HS_ULPI_NXT_45") (pintype "passive"))
      (node (ref "U2") (pin "16") (pinfunction "SCLK_16") (pintype "passive"))
      (node (ref "U3") (pin "6") (pinfunction "SCL_6") (pintype "passive"))
    )
    (net (code "67") (name "/IIC_SDA") (class "Default")
      (node (ref "U1") (pin "46") (pinfunction "PH5/I2C2_SDA/SPI5_NSS/FMC_SDNWE_46") (pintype "passive"))
      (node (ref "U2") (pin "17") (pinfunction "SDIN_17") (pintype "passive"))
      (node (ref "U3") (pin "5") (pinfunction "SDA_5") (pintype "passive"))
    )
    (net (code "68") (name "/JTCK") (class "Default")
      (node (ref "P10") (pin "2") (pinfunction "2_2") (pintype "passive"))
      (node (ref "R9") (pin "1") (pintype "passive"))
      (node (ref "U1") (pin "137") (pinfunction "PA14/JTCK/SWDCLK_137") (pintype "passive"))
    )
    (net (code "69") (name "/JTDO") (class "Default")
      (node (ref "P10") (pin "3") (pinfunction "3_3") (pintype "passive"))
      (node (ref "R10") (pin "1") (pintype "passive"))
    )
    (net (code "70") (name "/JTMS") (class "Default")
      (node (ref "P10") (pin "4") (pinfunction "4_4") (pintype "passive"))
      (node (ref "R11") (pin "1") (pintype "passive"))
      (node (ref "U1") (pin "124") (pinfunction "PA13/JTMS/SWDIO_124") (pintype "passive"))
    )
    (net (code "71") (name "/LCD_B4") (class "Default")
      (node (ref "J1") (pin "25") (pinfunction "25_25") (pintype "passive"))
      (node (ref "U1") (pin "173") (pinfunction "PI4/TIM8_BKIN/SAI2_MCK_A/FMC_NBL2/DCMI_D5/LCD_B4_173") (pintype "passive"))
    )
    (net (code "72") (name "/LCD_B5") (class "Default")
      (node (ref "J1") (pin "26") (pinfunction "26_26") (pintype "passive"))
      (node (ref "U1") (pin "174") (pinfunction "PI5/TIM8_CH1/SAI2_SCK_A/FMC_NBL3/DCMI_VSYNC/LCD_B5_174") (pintype "passive"))
    )
    (net (code "73") (name "/LCD_B6") (class "Default")
      (node (ref "J1") (pin "27") (pinfunction "27_27") (pintype "passive"))
      (node (ref "U1") (pin "175") (pinfunction "PI6/TIM8_CH2/SAI2_SD_A/FMC_D28/DCMI_D6/LCD_B6_175") (pintype "passive"))
    )
    (net (code "74") (name "/LCD_B7") (class "Default")
      (node (ref "J1") (pin "28") (pinfunction "28_28") (pintype "passive"))
      (node (ref "U1") (pin "176") (pinfunction "PI7/TIM8_CH3/SAI2_FS_A/FMC_D29/DCMI_D7/LCD_B7_176") (pintype "passive"))
    )
    (net (code "75") (name "/LCD_BL") (class "Default")
      (node (ref "J1") (pin "34") (pinfunction "34_34") (pintype "passive"))
      (node (ref "LCD1") (pin "23") (pinfunction "BL_23") (pintype "passive"))
      (node (ref "R28") (pin "2") (pintype "passive"))
      (node (ref "U1") (pin "56") (pinfunction "PB0/TIM1_CH2N/TIM3_CH3/TIM8_CH2N/DFSDM_CKOUT/U4_CTS/LCD_R3/OTG_HS_ULPI_D1/ETH_MII_RXD2/LCD_G1/ADC12_IN8_56") (pintype "passive"))
    )
    (net (code "76") (name "/LCD_G2") (class "Default")
      (node (ref "J1") (pin "14") (pinfunction "14_14") (pintype "passive"))
      (node (ref "U1") (pin "128") (pinfunction "PH13/TIM8_CH1N/U4_TX/CAN1_TX/FMC_D21/LCD_G2_128") (pintype "passive"))
    )
    (net (code "77") (name "/LCD_G3") (class "Default")
      (node (ref "J1") (pin "15") (pinfunction "15_15") (pintype "passive"))
      (node (ref "U1") (pin "129") (pinfunction "PH14/TIM8_CH2N/U4_RX/CAN1_RX/FMC_D22/DCMI_D4/LCD_G3_129") (pintype "passive"))
    )
    (net (code "78") (name "/LCD_G4") (class "Default")
      (node (ref "J1") (pin "16") (pinfunction "16_16") (pintype "passive"))
      (node (ref "U1") (pin "130") (pinfunction "PH15/TIM8_CH3N/FMC_D23/DCMI_D11/LCD_G4_130") (pintype "passive"))
    )
    (net (code "79") (name "/LCD_G5") (class "Default")
      (node (ref "J1") (pin "17") (pinfunction "17_17") (pintype "passive"))
      (node (ref "U1") (pin "131") (pinfunction "PI0/TIM5_CH4/SPI2_NSS/I2S2_WS/FMC_D24/DCMI_D13/LCD_G5_131") (pintype "passive"))
    )
    (net (code "80") (name "/LCD_G6") (class "Default")
      (node (ref "J1") (pin "18") (pinfunction "18_18") (pintype "passive"))
      (node (ref "U1") (pin "132") (pinfunction "PI1/TIM8_BKIN2/SPI2_SCK/I2S2_CK/FMC_D25/DCMI_D8/LCD_G6_132") (pintype "passive"))
    )
    (net (code "81") (name "/LCD_G7") (class "Default")
      (node (ref "J1") (pin "19") (pinfunction "19_19") (pintype "passive"))
      (node (ref "U1") (pin "133") (pinfunction "PI2/TIM8_CH4/SPI2_MISO/FMC_D26/DCMI_D9/LCD_G7_133") (pintype "passive"))
    )
    (net (code "82") (name "/LCD_HSYNC") (class "Default")
      (node (ref "J1") (pin "31") (pinfunction "31_31") (pintype "passive"))
      (node (ref "U1") (pin "12") (pinfunction "PI10/ETH_MII_RX_ER/FMC_D31/LCD_HSYNC_12") (pintype "passive"))
    )
    (net (code "83") (name "/LCD_R3") (class "Default")
      (node (ref "J1") (pin "6") (pinfunction "6_6") (pintype "passive"))
      (node (ref "U1") (pin "86") (pinfunction "PH9/I2C3_SMBA/TIM12_CH2/FMC_D17/DCMI_D0/LCD_R3_86") (pintype "passive"))
    )
    (net (code "84") (name "/LCD_R4") (class "Default")
      (node (ref "J1") (pin "7") (pinfunction "7_7") (pintype "passive"))
      (node (ref "U1") (pin "87") (pinfunction "PH10/I2C4_SMBA/TIM5_CH1/FMC_D18/DCMI_D1/LCD_R4_87") (pintype "passive"))
    )
    (net (code "85") (name "/LCD_R5") (class "Default")
      (node (ref "J1") (pin "8") (pinfunction "8_8") (pintype "passive"))
      (node (ref "U1") (pin "88") (pinfunction "PH11/I2C4_SCL/TIM5_CH2/FMC_D19/DCMI_D2/LCD_R5_88") (pintype "passive"))
    )
    (net (code "86") (name "/LCD_R6") (class "Default")
      (node (ref "J1") (pin "9") (pinfunction "9_9") (pintype "passive"))
      (node (ref "U1") (pin "89") (pinfunction "PH12/I2C4_SDA/TIM5_CH3/FMC_D20/DCMI_D3/LCD_R6_89") (pintype "passive"))
    )
    (net (code "87") (name "/LCD_RESET") (class "Default")
      (node (ref "C5") (pin "2") (pintype "passive"))
      (node (ref "J1") (pin "40") (pinfunction "40_40") (pintype "passive"))
      (node (ref "LCD1") (pin "5") (pinfunction "RST_5") (pintype "passive"))
      (node (ref "R2") (pin "2") (pintype "passive"))
      (node (ref "RST") (pin "1") (pinfunction "1_1") (pintype "passive"))
      (node (ref "U1") (pin "31") (pinfunction "NRST_31") (pintype "passive"))
    )
    (net (code "88") (name "/LCD_VSYNC") (class "Default")
      (node (ref "J1") (pin "32") (pinfunction "32_32") (pintype "passive"))
      (node (ref "U1") (pin "11") (pinfunction "PI9/U4_RX/CAN1_RX/FMC_D30/LCD_VSYNC_11") (pintype "passive"))
    )
    (net (code "89") (name "/LED0") (class "Default")
      (node (ref "DS0") (pin "2") (pinfunction "K_2") (pintype "passive"))
      (node (ref "U1") (pin "107") (pinfunction "PG3/FMC_A13_107") (pintype "passive"))
    )
    (net (code "90") (name "/LED1") (class "Default")
      (node (ref "DS1") (pin "2") (pinfunction "K_2") (pintype "passive"))
      (node (ref "U1") (pin "134") (pinfunction "PI3/TIM8_ETR/SPI2_MOSI/I2S2_SD/FMC_D27/DCMI_D10_134") (pintype "passive"))
    )
    (net (code "91") (name "/PA0") (class "Default")
      (node (ref "U1") (pin "40") (pinfunction "PA0/WKUP1/TIM2_CH1/TIM2_ETR/TIM5_CH1/TIM8_ETR/U2_CTS/U4_TX/SAI2_SD_B/ETH_MII_CRS/ADC123_IN0_40") (pintype "passive"))
    )
    (net (code "92") (name "/PA1") (class "Default")
      (node (ref "R40") (pin "1") (pintype "passive"))
      (node (ref "U1") (pin "41") (pinfunction "PA1/TIM2_CH2/TIM5_CH2/U2_RTS/U4_RX/QSPI_BK1_IO3/SAI2_MCK_B/ETH_MII_RX_CLK/ETH_RMII_REF_CLK/LCD_R2/ADC123_IN1_41") (pintype "passive"))
    )
    (net (code "93") (name "/PA2") (class "Default")
      (node (ref "PA2") (pin "1") (pinfunction "1_1") (pintype "passive"))
      (node (ref "U1") (pin "42") (pinfunction "PA2/TIM2_CH3/TIM5_CH3/TIM9_CH1/U2_TX/SAI2_SCK_B/ETH_MDIO/LCD_R1/ADC123_IN2/WKUP2_42") (pintype "passive"))
    )
    (net (code "94") (name "/PA3") (class "Default")
      (node (ref "PA3") (pin "1") (pinfunction "1_1") (pintype "passive"))
      (node (ref "U1") (pin "47") (pinfunction "PA3/TIM2_CH4/TIM5_CH4/TIM9_CH2/U2_RX/OTG_HS_ULPI_D0/ETH_MII_COL/LCD_B2/LCD_B5/ADC123_IN3_47") (pintype "passive"))
    )
    (net (code "95") (name "/PA4") (class "Default")
      (node (ref "J1") (pin "36") (pinfunction "36_36") (pintype "passive"))
      (node (ref "LCD1") (pin "30") (pinfunction "MOSI_30") (pintype "passive"))
      (node (ref "U1") (pin "50") (pinfunction "PA4/SPI1_NSS/I2S1_WS/SPI3_NSS/I2S3_WS/U2_CK/SPI6_NSS/OTG_HS_SOF/DCMI_HSYNC/LCD_VSYNC/ADC12_IN4/DAC_OUT1_50") (pintype "passive"))
    )
    (net (code "96") (name "/PA5") (class "Default")
      (node (ref "J1") (pin "37") (pinfunction "37_37") (pintype "passive"))
      (node (ref "LCD1") (pin "29") (pinfunction "MISO_29") (pintype "passive"))
      (node (ref "U1") (pin "51") (pinfunction "PA5/TIM2_CH1/TIM2_ETR/TIM8_CH1N/SPI1_SCK/I2S1_CK/SPI6_SCK/OTG_HS_ULPI_CK/LCD_R4/ADC12_IN5/DAC_OUT2_51") (pintype "passive"))
    )
    (net (code "97") (name "/PA6") (class "Default")
      (node (ref "U1") (pin "52") (pinfunction "PA6/TIM1_BKIN/TIM3_CH1/TIM8_BKIN/SPI1_MISO/SPI6_MISO/TIM13_CH1/DCMI_PIXCLK/LCD_G2/ADC12_IN6_52") (pintype "passive"))
    )
    (net (code "98") (name "/PA7") (class "Default")
      (node (ref "J1") (pin "39") (pinfunction "39_39") (pintype "passive"))
      (node (ref "LCD1") (pin "31") (pinfunction "T_PEN_31") (pintype "passive"))
      (node (ref "U1") (pin "53") (pinfunction "PA7/TIM1_CH1N/TIM3_CH2/TIM8_CH1N/SPI1_MOSI/I2S1_SD/SPI6_MOSI/TIM14_CH1/ETH_MII_RX_DV/ETH_RMII_CRS_DV/FMC_SDNWE/ADC12_IN7_53") (pintype "passive"))
    )
    (net (code "99") (name "/PA8") (class "Default")
      (node (ref "U1") (pin "119") (pinfunction "PA8/MCO1/TIM1_CH1/TIM8_BKIN2/I2C3_SCL/U1_CK/OTG_FS_SOF/CAN3_RX/U7_RX/LCD_B3/LCD_R6_119") (pintype "passive"))
    )
    (net (code "100") (name "/PA9") (class "Default")
      (node (ref "P4") (pin "3") (pinfunction "3_3") (pintype "passive"))
      (node (ref "U1") (pin "120") (pinfunction "PA9/TIM1_CH2/I2C3_SMBA/SPI2_SCK/I2S2_CK/U1_TX/DCMI_D0/LCD_R5/OTG_FS_VBUS_120") (pintype "passive"))
    )
    (net (code "101") (name "/PA10") (class "Default")
      (node (ref "P4") (pin "1") (pinfunction "1_1") (pintype "passive"))
      (node (ref "U1") (pin "121") (pinfunction "PA10/TIM1_CH3/U1_RX/LCD_B4/LCD_B1/OTG_FS_ID/DCMI_D1_121") (pintype "passive"))
    )
    (net (code "102") (name "/PA11") (class "Default")
      (node (ref "R12") (pin "2") (pintype "passive"))
      (node (ref "U1") (pin "122") (pinfunction "PA11/TIM1_CH4/SPI2_NSS/I2S2_WS/U4_RX/U1_CTS/CAN1_RX/LCD_R4/OTG_FS_DM_122") (pintype "passive"))
    )
    (net (code "103") (name "/PA12") (class "Default")
      (node (ref "R14") (pin "2") (pintype "passive"))
      (node (ref "U1") (pin "123") (pinfunction "PA12/TIM1_ETR/SPI2_SCK/I2S2_CK/U4_TX/U1_RTS/SAI2_FS_B/CAN1_TX/LCD_R5/OTG_FS_DP_123") (pintype "passive"))
    )
    (net (code "104") (name "/PA15") (class "Default")
      (node (ref "U1") (pin "138") (pinfunction "PA15/JTDI/TIM2_CH1/TIM2_ETR/HDMI_CEC/SPI1_NSS/I2S1_WS/SPI3_NSS/I2S3_WS/SPI6_NSS/U4_RTS/CAN3_TX/U7_TX_138") (pintype "passive"))
    )
    (net (code "105") (name "/PB1") (class "Default")
      (node (ref "U1") (pin "57") (pinfunction "PB1/TIM1_CH3N/TIM3_CH4/TIM8_CH3N/DFSDM_D1/LCD_R6/OTG_HS_ULPI_D2/ETH_MII_RXD3/LCD_G0/ADC12_IN9_57") (pintype "passive"))
    )
    (net (code "106") (name "/PB2") (class "Default")
      (node (ref "U1") (pin "58") (pinfunction "PB2/SAI1_SD_A/SPI3_MOSI/I2S3_SD/QSPI_CLK/DFSDM_CKIN1_58") (pintype "passive"))
      (node (ref "U4") (pin "6") (pinfunction "CLK_6") (pintype "passive"))
    )
    (net (code "107") (name "/PB3") (class "Default")
      (node (ref "U1") (pin "161") (pinfunction "PB3/JTDO/TIM2_CH2/SPI1_SCK/I2S1_CK/SPI3_SCK/I2S3_CK/SPI6_SCK/SDMMC2_D2/CAN3_RX/U7_RX_161") (pintype "passive"))
    )
    (net (code "108") (name "/PB4") (class "Default")
      (node (ref "U1") (pin "162") (pinfunction "PB4/NJTRST/TIM3_CH1/SPI1_MISO/SPI3_MISO/SPI2_NSS/I2S2_WS/SPI6_MISO/SDMMC2_D3/CAN3_TX/U7_TX_162") (pintype "passive"))
    )
    (net (code "109") (name "/PB6") (class "Default")
      (node (ref "U1") (pin "164") (pinfunction "PB6/U5_TX/TIM4_CH1/HDMI_CEC/I2C1_SCL/DFSDM_D5/U1_TX/CAN2_TX/QSPI_BK1_NCS/I2C4_SCL/FMC_SDNE1/DCMI_D5_164") (pintype "passive"))
      (node (ref "U4") (pin "1") (pinfunction "~{CS}_1") (pintype "passive"))
    )
    (net (code "110") (name "/PB7") (class "Default")
      (node (ref "U1") (pin "165") (pinfunction "PB7/TIM4_CH2/I2C1_SDA/DFSDM_CKIN5/U1_RX/I2C4_SDA/FMC_NL/DCMI_VSYNC_165") (pintype "passive"))
    )
    (net (code "111") (name "/PB10") (class "Default")
      (node (ref "U1") (pin "79") (pinfunction "PB10/TIM2_CH3/I2C2_SCL/SPI2_SCK/I2S2_CK/DFSDM_D7/U3_TX/QSPI_BK1_NCS/OTG_HS_ULPI_D3/ETH_MII_RX_ER/LCD_G4_79") (pintype "passive"))
    )
    (net (code "112") (name "/PB11") (class "Default")
      (node (ref "U1") (pin "80") (pinfunction "PB11/TIM2_CH4/I2C2_SDA/DFSDM_CKIN7/U3_RX/OTG_HS_ULPI_D4/ETH_MII_TX_EN/ETH_RMII_TX_EN/LCD_G5_80") (pintype "passive"))
    )
    (net (code "113") (name "/PB12") (class "Default")
      (node (ref "U1") (pin "92") (pinfunction "PB12/TIM1_BKIN/I2C2_SMBA/SPI2_NSS/I2S2_WS/DFSDM_D1/U3_CK/U5_RX/CAN2_RX/OTG_HS_ULPI_D5/ETH_MII_TXD0/ETH_RMII_TXD0/OTG_HS_ID_92") (pintype "passive"))
    )
    (net (code "114") (name "/PB13") (class "Default")
      (node (ref "U1") (pin "93") (pinfunction "PB13/TIM1_CH1N/SPI2_SCK/I2S2_CK/DFSDM_CKIN1/U3_CTS/U5_TX/CAN2_TX/OTG_HS_ULPI_D6/ETH_MII_TXD1/ETH_RMII_TXD1/OTG_HS_VBUS_93") (pintype "passive"))
    )
    (net (code "115") (name "/PB14") (class "Default")
      (node (ref "U1") (pin "94") (pinfunction "PB14/TIM1_CH2N/TIM8_CH2N/U1_TX/SPI2_MISO/DFSDM_D2/U3_RTS/U4_RTS/SDMMC2_D0/TIM12_CH1/OTG_HS_DM_94") (pintype "passive"))
    )
    (net (code "116") (name "/PB15") (class "Default")
      (node (ref "U1") (pin "95") (pinfunction "PB15/RTC_REFIN/TIM1_CH3N/TIM8_CH3N/U1_RX/SPI2_MOSI/I2S2_SD/DFSDM_CKIN2/U4_CTS/SDMMC2_D1/TIM12_CH2/OTG_HS_DP_95") (pintype "passive"))
    )
    (net (code "117") (name "/PC1") (class "Default")
      (node (ref "U1") (pin "33") (pinfunction "PC1/DFSDM_CKIN4/DFSDM_D0/SPI2_MOSI/I2S2_SD/SAI1_SD_A/ETH_MDC/ADC123_IN11/RTC_TAMP3/WKUP3_33") (pintype "passive"))
    )
    (net (code "118") (name "/PC4") (class "Default")
      (node (ref "J1") (pin "38") (pinfunction "38_38") (pintype "passive"))
      (node (ref "LCD1") (pin "34") (pinfunction "CLK_34") (pintype "passive"))
      (node (ref "U1") (pin "54") (pinfunction "PC4/DFSDM_CKIN2/I2S1_MCK/SPDIFRX_IN2/ETH_MII_RXD0/ETH_RMII_RXD0/FMC_SDNE0/ADC12_IN14_54") (pintype "passive"))
    )
    (net (code "119") (name "/PC5") (class "Default")
      (node (ref "J1") (pin "35") (pinfunction "35_35") (pintype "passive"))
      (node (ref "LCD1") (pin "33") (pinfunction "T_CS_33") (pintype "passive"))
      (node (ref "U1") (pin "55") (pinfunction "PC5/DFSDM_D2/SPDIFRX_IN3/ETH_MII_RXD1/ETH_RMII_RXD1/FMC_SDCKE0/ADC12_IN15_55") (pintype "passive"))
    )
    (net (code "120") (name "/PC6") (class "Default")
      (node (ref "U1") (pin "115") (pinfunction "PC6/DFSDM_CKIN3/TIM3_CH1/TIM8_CH1/I2S2_MCK/U6_TX/FMC_NWAIT/SDMMC12_D6/DCMI_D0/LCD_HSYNC_115") (pintype "passive"))
    )
    (net (code "121") (name "/PC7") (class "Default")
      (node (ref "U1") (pin "116") (pinfunction "PC7/DFSDM_D3/TIM3_CH2/TIM8_CH2/I2S3_MCK/U6_RX/FMC_NE1/SDMMC12_D7/DCMI_D1/LCD_G6_116") (pintype "passive"))
    )
    (net (code "122") (name "/PC8") (class "Default")
      (node (ref "R15") (pin "1") (pintype "passive"))
      (node (ref "TF_CARD") (pin "7") (pinfunction "DAT0/DO_7") (pintype "passive"))
      (node (ref "U1") (pin "117") (pinfunction "PC8/TIM3_CH3/TIM8_CH3/U5_RTS/U6_CK/FMC_NE2/FMC_NCE/SDMMC1_D0/DCMI_D2_117") (pintype "passive"))
    )
    (net (code "123") (name "/PC9") (class "Default")
      (node (ref "R19") (pin "1") (pintype "passive"))
      (node (ref "TF_CARD") (pin "8") (pinfunction "DAT1/IRQ_8") (pintype "passive"))
      (node (ref "U1") (pin "118") (pinfunction "PC9/MCO2/TIM3_CH4/TIM8_CH4/I2C3_SDA/I2S_CKIN/U5_CTS/QSPI_BK1_IO0/SDMMC1_D1/DCMI_D3/LCD_G3/LCD_B2_118") (pintype "passive"))
    )
    (net (code "124") (name "/PC10") (class "Default")
      (node (ref "R18") (pin "1") (pintype "passive"))
      (node (ref "TF_CARD") (pin "1") (pinfunction "DAT2/NC_1") (pintype "passive"))
      (node (ref "U1") (pin "139") (pinfunction "PC10/DFSDM_CKIN5/SPI3_SCK/I2S3_CK/U3_TX/U4_TX/QSPI_BK1_IO1/SDMMC1_D2/DCMI_D8/LCD_R2_139") (pintype "passive"))
    )
    (net (code "125") (name "/PC11") (class "Default")
      (node (ref "R17") (pin "1") (pintype "passive"))
      (node (ref "TF_CARD") (pin "2") (pinfunction "CS/DATA3_2") (pintype "passive"))
      (node (ref "U1") (pin "140") (pinfunction "PC11/DFSDM_D5/SPI3_MISO/U3_RX/U4_RX/QSPI_BK2_NCS/SDMMC1_D3/DCMI_D4_140") (pintype "passive"))
    )
    (net (code "126") (name "/PC12") (class "Default")
      (node (ref "TF_CARD") (pin "5") (pinfunction "CLK_5") (pintype "passive"))
      (node (ref "U1") (pin "141") (pinfunction "PC12/SPI3_MOSI/I2S3_SD/U3_CK/U5_TX/SDMMC1_CK/DCMI_D9_141") (pintype "passive"))
    )
    (net (code "127") (name "/PC13") (class "Default")
      (node (ref "U1") (pin "8") (pinfunction "PC13/RTC_TAMP1/RTC_TS/RTC_OUT/WKUP4_8") (pintype "passive"))
    )
    (net (code "128") (name "/PC14") (class "Default")
      (node (ref "C3") (pin "2") (pintype "passive"))
      (node (ref "U1") (pin "9") (pinfunction "PC14/OSC32_IN_9") (pintype "passive"))
      (node (ref "Y2") (pin "2") (pinfunction "OSC2_2") (pintype "passive"))
    )
    (net (code "129") (name "/PC15") (class "Default")
      (node (ref "C4") (pin "2") (pintype "passive"))
      (node (ref "U1") (pin "10") (pinfunction "PC15/OSC32_OUT_10") (pintype "passive"))
      (node (ref "Y2") (pin "1") (pinfunction "OSC1_1") (pintype "passive"))
    )
    (net (code "130") (name "/PD2") (class "Default")
      (node (ref "R16") (pin "1") (pintype "passive"))
      (node (ref "TF_CARD") (pin "3") (pinfunction "CMD_3") (pintype "passive"))
      (node (ref "U1") (pin "144") (pinfunction "PD2/TIM3_ETR/U5_RX/SDMMC1_CMD/DCMI_D11_144") (pintype "passive"))
    )
    (net (code "131") (name "/PE2") (class "Default")
      (node (ref "U1") (pin "1") (pinfunction "PE2/SPI4_SCK/SAI1_MCLK_A/QSPI_BK1_IO2/ETH_MII_TXD3/FMC_A23_1") (pintype "passive"))
      (node (ref "U2") (pin "11") (pinfunction "MCLK_11") (pintype "passive"))
    )
    (net (code "132") (name "/PE3") (class "Default")
      (node (ref "U1") (pin "2") (pinfunction "PE3/SAI1_SD_B/FMC_A19_2") (pintype "passive"))
      (node (ref "U2") (pin "9") (pinfunction "ADCDAT_9") (pintype "passive"))
    )
    (net (code "133") (name "/PE4") (class "Default")
      (node (ref "U1") (pin "3") (pinfunction "PE4/DFSDM_D3/SPI4_NSS/SAI1_FS_A/FMC_A20/DCMI_D4/LCD_B0_3") (pintype "passive"))
      (node (ref "U2") (pin "7") (pinfunction "LRC_7") (pintype "passive"))
    )
    (net (code "134") (name "/PE5") (class "Default")
      (node (ref "U1") (pin "4") (pinfunction "PE5/DFSDM_CKIN3/TIM9_CH1/SPI4_MISO/SAI1_SCK_A/FMC_A21/DCMI_D6/LCD_G0_4") (pintype "passive"))
      (node (ref "U2") (pin "8") (pinfunction "BCLK_8") (pintype "passive"))
    )
    (net (code "135") (name "/PE6") (class "Default")
      (node (ref "U1") (pin "5") (pinfunction "PE6/TIM1_BKIN2/TIM9_CH2/SPI4_MOSI/SAI1_SD_A/SAI2_MCK_B/FMC_A22/DCMI_D7/LCD_G1_5") (pintype "passive"))
      (node (ref "U2") (pin "10") (pinfunction "DACDAT_10") (pintype "passive"))
    )
    (net (code "136") (name "/PG13") (class "Default")
      (node (ref "U1") (pin "156") (pinfunction "PG13/LPTIM1_OUT/SPI6_SCK/U6_CTS/ETH_MII_TXD0/ETH_RMII_TXD0/FMC_A24/LCD_R0_156") (pintype "passive"))
    )
    (net (code "137") (name "/PG14") (class "Default")
      (node (ref "U1") (pin "157") (pinfunction "PG14/LPTIM1_ETR/SPI6_MOSI/U6_TX/QSPI_BK2_IO3/ETH_MII_TXD1/ETH_RMII_TXD1/FMC_A25/LCD_B0_157") (pintype "passive"))
    )
    (net (code "138") (name "/PH0") (class "Default")
      (node (ref "C1") (pin "1") (pintype "passive"))
      (node (ref "U1") (pin "29") (pinfunction "PH0/OSC_IN_29") (pintype "passive"))
      (node (ref "Y1") (pin "2") (pinfunction "OSC2_2") (pintype "passive"))
    )
    (net (code "139") (name "/PH1") (class "Default")
      (node (ref "C2") (pin "1") (pintype "passive"))
      (node (ref "U1") (pin "30") (pinfunction "PH1/OSC_OUT_30") (pintype "passive"))
      (node (ref "Y1") (pin "1") (pinfunction "OSC1_1") (pintype "passive"))
    )
    (net (code "140") (name "/PH2") (class "Default")
      (node (ref "U1") (pin "43") (pinfunction "PH2/LPTIM1_IN2/QSPI_BK2_IO0/SAI2_SCK_B/ETH_MII_CRS/FMC_SDCKE0/LCD_R0_43") (pintype "passive"))
    )
    (net (code "141") (name "/PH3") (class "Default")
      (node (ref "U1") (pin "44") (pinfunction "PH3/QSPI_BK2_IO1/SAI2_MCK_B/ETH_MII_COL/FMC_SDNE0/LCD_R1_44") (pintype "passive"))
    )
    (net (code "142") (name "/PH6") (class "Default")
      (node (ref "U1") (pin "83") (pinfunction "PH6/I2C2_SMBA/SPI5_SCK/TIM12_CH1/ETH_MII_RXD2/FMC_SDNE1/DCMI_D8_83") (pintype "passive"))
    )
    (net (code "143") (name "/PH7") (class "Default")
      (node (ref "U1") (pin "84") (pinfunction "PH7/I2C3_SCL/SPI5_MISO/ETH_MII_RXD3/FMC_SDCKE1/DCMI_D9_84") (pintype "passive"))
    )
    (net (code "144") (name "/PH8") (class "Default")
      (node (ref "U1") (pin "85") (pinfunction "PH8/I2C3_SDA/FMC_D16/DCMI_HSYNC/LCD_R2_85") (pintype "passive"))
    )
    (net (code "145") (name "/PI11") (class "Default")
      (node (ref "U1") (pin "13") (pinfunction "PI11/LCD_G6/OTG_HS_ULPI_DIR/WKUP6_13") (pintype "passive"))
    )
    (net (code "146") (name "/VUSB") (class "Default")
      (node (ref "POWER") (pin "2") (pinfunction "TAP_2") (pintype "passive"))
      (node (ref "USB_232") (pin "1") (pinfunction "VCC_1") (pintype "passive"))
      (node (ref "USB_SLAVE") (pin "1") (pinfunction "VCC_1") (pintype "passive"))
    )
    (net (code "147") (name "AGND") (class "Default")
      (node (ref "AUX") (pin "3") (pinfunction "COM_3") (pintype "passive"))
      (node (ref "C51") (pin "2") (pintype "passive"))
      (node (ref "C52") (pin "2") (pintype "passive"))
      (node (ref "C67") (pin "1") (pintype "passive"))
      (node (ref "C68") (pin "1") (pintype "passive"))
      (node (ref "MIC1") (pin "3") (pinfunction "COM_3") (pintype "passive"))
      (node (ref "PHONE") (pin "3") (pinfunction "COM_3") (pintype "passive"))
      (node (ref "R31") (pin "2") (pintype "passive"))
      (node (ref "R34") (pin "1") (pintype "passive"))
      (node (ref "R35") (pin "1") (pintype "passive"))
      (node (ref "R66") (pin "1") (pintype "passive"))
      (node (ref "U2") (pin "28") (pinfunction "AGND_28") (pintype "passive"))
    )
    (net (code "148") (name "GND") (class "Default")
      (node (ref "C1") (pin "2") (pintype "passive"))
      (node (ref "C10") (pin "1") (pintype "passive"))
      (node (ref "C11") (pin "1") (pintype "passive"))
      (node (ref "C12") (pin "1") (pintype "passive"))
      (node (ref "C13") (pin "1") (pintype "passive"))
      (node (ref "C14") (pin "1") (pintype "passive"))
      (node (ref "C15") (pin "1") (pintype "passive"))
      (node (ref "C16") (pin "1") (pintype "passive"))
      (node (ref "C17") (pin "1") (pintype "passive"))
      (node (ref "C18") (pin "1") (pintype "passive"))
      (node (ref "C19") (pin "1") (pintype "passive"))
      (node (ref "C2") (pin "2") (pintype "passive"))
      (node (ref "C20") (pin "1") (pintype "passive"))
      (node (ref "C21") (pin "1") (pintype "passive"))
      (node (ref "C22") (pin "1") (pintype "passive"))
      (node (ref "C23") (pin "1") (pintype "passive"))
      (node (ref "C24") (pin "1") (pintype "passive"))
      (node (ref "C25") (pin "1") (pintype "passive"))
      (node (ref "C26") (pin "1") (pintype "passive"))
      (node (ref "C27") (pin "1") (pintype "passive"))
      (node (ref "C28") (pin "1") (pintype "passive"))
      (node (ref "C29") (pin "1") (pintype "passive"))
      (node (ref "C3") (pin "1") (pintype "passive"))
      (node (ref "C30") (pin "2") (pintype "passive"))
      (node (ref "C31") (pin "2") (pintype "passive"))
      (node (ref "C32") (pin "2") (pintype "passive"))
      (node (ref "C33") (pin "1") (pintype "passive"))
      (node (ref "C34") (pin "1") (pintype "passive"))
      (node (ref "C35") (pin "2") (pinfunction "GND_2") (pintype "passive"))
      (node (ref "C36") (pin "2") (pintype "passive"))
      (node (ref "C38") (pin "2") (pintype "passive"))
      (node (ref "C39") (pin "2") (pintype "passive"))
      (node (ref "C4") (pin "1") (pintype "passive"))
      (node (ref "C40") (pin "1") (pintype "passive"))
      (node (ref "C41") (pin "1") (pintype "passive"))
      (node (ref "C42") (pin "1") (pintype "passive"))
      (node (ref "C43") (pin "1") (pintype "passive"))
      (node (ref "C44") (pin "1") (pintype "passive"))
      (node (ref "C45") (pin "1") (pintype "passive"))
      (node (ref "C46") (pin "1") (pintype "passive"))
      (node (ref "C47") (pin "1") (pintype "passive"))
      (node (ref "C48") (pin "1") (pintype "passive"))
      (node (ref "C49") (pin "2") (pintype "passive"))
      (node (ref "C5") (pin "1") (pintype "passive"))
      (node (ref "C50") (pin "1") (pintype "passive"))
      (node (ref "C55") (pin "1") (pintype "passive"))
      (node (ref "C56") (pin "1") (pintype "passive"))
      (node (ref "C57") (pin "1") (pintype "passive"))
      (node (ref "C58") (pin "1") (pintype "passive"))
      (node (ref "C6") (pin "1") (pintype "passive"))
      (node (ref "C69") (pin "1") (pintype "passive"))
      (node (ref "C7") (pin "1") (pintype "passive"))
      (node (ref "C8") (pin "1") (pintype "passive"))
      (node (ref "C9") (pin "1") (pintype "passive"))
      (node (ref "J1") (pin "11") (pinfunction "11_11") (pintype "passive"))
      (node (ref "J1") (pin "12") (pinfunction "12_12") (pintype "passive"))
      (node (ref "J1") (pin "13") (pinfunction "13_13") (pintype "passive"))
      (node (ref "J1") (pin "20") (pinfunction "20_20") (pintype "passive"))
      (node (ref "J1") (pin "21") (pinfunction "21_21") (pintype "passive"))
      (node (ref "J1") (pin "22") (pinfunction "22_22") (pintype "passive"))
      (node (ref "J1") (pin "23") (pinfunction "23_23") (pintype "passive"))
      (node (ref "J1") (pin "29") (pinfunction "29_29") (pintype "passive"))
      (node (ref "J1") (pin "3") (pinfunction "3_3") (pintype "passive"))
      (node (ref "J1") (pin "4") (pinfunction "4_4") (pintype "passive"))
      (node (ref "J1") (pin "5") (pinfunction "5_5") (pintype "passive"))
      (node (ref "LCD1") (pin "22") (pinfunction "GND_22") (pintype "passive"))
      (node (ref "LCD1") (pin "26") (pinfunction "GND_26") (pintype "passive"))
      (node (ref "LCD1") (pin "27") (pinfunction "GND_27") (pintype "passive"))
      (node (ref "P10") (pin "1") (pinfunction "1_1") (pintype "passive"))
      (node (ref "PWR") (pin "2") (pinfunction "K_2") (pintype "passive"))
      (node (ref "R1") (pin "2") (pintype "passive"))
      (node (ref "R28") (pin "1") (pintype "passive"))
      (node (ref "R31") (pin "1") (pintype "passive"))
      (node (ref "R32") (pin "1") (pintype "passive"))
      (node (ref "R8") (pin "2") (pintype "passive"))
      (node (ref "R9") (pin "2") (pintype "passive"))
      (node (ref "RST") (pin "2") (pinfunction "2_2") (pintype "passive"))
      (node (ref "TF_CARD") (pin "6") (pinfunction "VSS_6") (pintype "passive"))
      (node (ref "U1") (pin "102") (pinfunction "VSS_102") (pintype "passive"))
      (node (ref "U1") (pin "113") (pinfunction "VSS_113") (pintype "passive"))
      (node (ref "U1") (pin "126") (pinfunction "VSS_126") (pintype "passive"))
      (node (ref "U1") (pin "135") (pinfunction "VSS_135") (pintype "passive"))
      (node (ref "U1") (pin "14") (pinfunction "VSS_14") (pintype "passive"))
      (node (ref "U1") (pin "148") (pinfunction "VSS_148") (pintype "passive"))
      (node (ref "U1") (pin "158") (pinfunction "VSS_158") (pintype "passive"))
      (node (ref "U1") (pin "22") (pinfunction "VSS_22") (pintype "passive"))
      (node (ref "U1") (pin "37") (pinfunction "VSSA_37") (pintype "passive"))
      (node (ref "U1") (pin "61") (pinfunction "VSS_61") (pintype "passive"))
      (node (ref "U1") (pin "71") (pinfunction "VSS_71") (pintype "passive"))
      (node (ref "U1") (pin "90") (pinfunction "VSS_90") (pintype "passive"))
      (node (ref "U10") (pin "13") (pinfunction "VSS_13") (pintype "passive"))
      (node (ref "U10") (pin "36") (pinfunction "VSS_36") (pintype "passive"))
      (node (ref "U11") (pin "12") (pinfunction "VSSQ1_12") (pintype "power_in"))
      (node (ref "U11") (pin "28") (pinfunction "VSS2_28") (pintype "power_in"))
      (node (ref "U11") (pin "41") (pinfunction "VSS0_41") (pintype "power_in"))
      (node (ref "U11") (pin "46") (pinfunction "VSSQ2_46") (pintype "power_in"))
      (node (ref "U11") (pin "52") (pinfunction "VSSQ3_52") (pintype "power_in"))
      (node (ref "U11") (pin "54") (pinfunction "VSS1_54") (pintype "power_in"))
      (node (ref "U11") (pin "6") (pinfunction "VSSQ0_6") (pintype "power_in"))
      (node (ref "U12") (pin "1") (pinfunction "GND_1") (pintype "passive"))
      (node (ref "U14") (pin "1") (pinfunction "GND_1") (pintype "passive"))
      (node (ref "U2") (pin "12") (pinfunction "DGND_12") (pintype "passive"))
      (node (ref "U2") (pin "24") (pinfunction "SPKGND_24") (pintype "passive"))
      (node (ref "U2") (pin "33") (pinfunction "GNDPAD_33") (pintype "passive"))
      (node (ref "U3") (pin "1") (pinfunction "A0_1") (pintype "passive"))
      (node (ref "U3") (pin "2") (pinfunction "A1_2") (pintype "passive"))
      (node (ref "U3") (pin "3") (pinfunction "A2_3") (pintype "passive"))
      (node (ref "U3") (pin "4") (pinfunction "GND_4") (pintype "passive"))
      (node (ref "U3") (pin "7") (pinfunction "WP_7") (pintype "passive"))
      (node (ref "U4") (pin "4") (pinfunction "GND_4") (pintype "passive"))
      (node (ref "U6") (pin "3") (pinfunction "NC_3") (pintype "passive"))
      (node (ref "U6") (pin "4") (pinfunction "GND_4") (pintype "passive"))
      (node (ref "USB_232") (pin "5") (pinfunction "GND_5") (pintype "passive"))
      (node (ref "USB_SLAVE") (pin "5") (pinfunction "GND_5") (pintype "passive"))
    )
    (net (code "149") (name "Net-(AUX-CHL)") (class "Default")
      (node (ref "AUX") (pin "1") (pinfunction "CHL_1") (pintype "passive"))
      (node (ref "C66") (pin "2") (pintype "passive"))
    )
    (net (code "150") (name "Net-(AUX-CHR)") (class "Default")
      (node (ref "AUX") (pin "2") (pinfunction "CHR_2") (pintype "passive"))
      (node (ref "C65") (pin "2") (pintype "passive"))
    )
    (net (code "151") (name "Net-(C40-Pad2)") (class "Default")
      (node (ref "C40") (pin "2") (pintype "passive"))
      (node (ref "C41") (pin "2") (pintype "passive"))
      (node (ref "R20") (pin "1") (pintype "passive"))
      (node (ref "U10") (pin "12") (pinfunction "VCC_12") (pintype "passive"))
      (node (ref "U10") (pin "37") (pinfunction "VCC_37") (pintype "passive"))
    )
    (net (code "152") (name "Net-(C53-GND)") (class "Default")
      (node (ref "C53") (pin "2") (pinfunction "GND_2") (pintype "passive"))
      (node (ref "PHONE") (pin "2") (pinfunction "CHR_2") (pintype "passive"))
    )
    (net (code "153") (name "Net-(C53-VCC)") (class "Default")
      (node (ref "C53") (pin "1") (pinfunction "VCC_1") (pintype "passive"))
      (node (ref "U2") (pin "29") (pinfunction "ROUT1_29") (pintype "passive"))
    )
    (net (code "154") (name "Net-(C54-GND)") (class "Default")
      (node (ref "C54") (pin "2") (pinfunction "GND_2") (pintype "passive"))
      (node (ref "PHONE") (pin "1") (pinfunction "CHL_1") (pintype "passive"))
    )
    (net (code "155") (name "Net-(C54-VCC)") (class "Default")
      (node (ref "C54") (pin "1") (pinfunction "VCC_1") (pintype "passive"))
      (node (ref "U2") (pin "30") (pinfunction "LOUT1_30") (pintype "passive"))
    )
    (net (code "156") (name "Net-(DS0-A)") (class "Default")
      (node (ref "DS0") (pin "1") (pinfunction "A_1") (pintype "passive"))
      (node (ref "R37") (pin "1") (pintype "passive"))
    )
    (net (code "157") (name "Net-(DS1-A)") (class "Default")
      (node (ref "DS1") (pin "1") (pinfunction "A_1") (pintype "passive"))
      (node (ref "R38") (pin "1") (pintype "passive"))
    )
    (net (code "158") (name "Net-(MIC-GND)") (class "Default")
      (node (ref "C61") (pin "2") (pintype "passive"))
      (node (ref "C63") (pin "2") (pintype "passive"))
      (node (ref "MIC") (pin "2") (pinfunction "GND_2") (pintype "passive"))
      (node (ref "R33") (pin "2") (pintype "passive"))
      (node (ref "R34") (pin "2") (pintype "passive"))
      (node (ref "R66") (pin "2") (pintype "passive"))
    )
    (net (code "159") (name "Net-(MIC-VCC)") (class "Default")
      (node (ref "C62") (pin "2") (pintype "passive"))
      (node (ref "C64") (pin "2") (pintype "passive"))
      (node (ref "MIC") (pin "1") (pinfunction "VCC_1") (pintype "passive"))
      (node (ref "R35") (pin "2") (pintype "passive"))
    )
    (net (code "160") (name "Net-(MIC1-CHL)") (class "Default")
      (node (ref "C60") (pin "2") (pintype "passive"))
      (node (ref "MIC1") (pin "1") (pinfunction "CHL_1") (pintype "passive"))
    )
    (net (code "161") (name "Net-(MIC1-CHR)") (class "Default")
      (node (ref "C59") (pin "2") (pintype "passive"))
      (node (ref "MIC1") (pin "2") (pinfunction "CHR_2") (pintype "passive"))
    )
    (net (code "162") (name "Net-(PWR-A)") (class "Default")
      (node (ref "PWR") (pin "1") (pinfunction "A_1") (pintype "passive"))
      (node (ref "R39") (pin "1") (pintype "passive"))
    )
    (net (code "163") (name "Net-(U1-BYPASS_REG)") (class "Default")
      (node (ref "R1") (pin "1") (pintype "passive"))
      (node (ref "U1") (pin "48") (pinfunction "BYPASS_REG_48") (pintype "passive"))
    )
    (net (code "164") (name "Net-(U1-PDR_ON)") (class "Default")
      (node (ref "R5") (pin "1") (pintype "passive"))
      (node (ref "U1") (pin "171") (pinfunction "PDR_ON_171") (pintype "passive"))
    )
    (net (code "165") (name "Net-(U1-VBAT)") (class "Default")
      (node (ref "C8") (pin "2") (pintype "passive"))
      (node (ref "D1") (pin "2") (pintype "passive"))
      (node (ref "U1") (pin "6") (pinfunction "VBAT_6") (pintype "passive"))
    )
    (net (code "166") (name "Net-(U1-VCAP_1)") (class "Default")
      (node (ref "C6") (pin "2") (pintype "passive"))
      (node (ref "U1") (pin "81") (pinfunction "VCAP_1_81") (pintype "passive"))
    )
    (net (code "167") (name "Net-(U1-VCAP_2)") (class "Default")
      (node (ref "C7") (pin "2") (pintype "passive"))
      (node (ref "U1") (pin "125") (pinfunction "VCAP_2_125") (pintype "passive"))
    )
    (net (code "168") (name "Net-(U1-VDDA)") (class "Default")
      (node (ref "C11") (pin "2") (pintype "passive"))
      (node (ref "C12") (pin "2") (pintype "passive"))
      (node (ref "R3") (pin "1") (pintype "passive"))
      (node (ref "R4") (pin "1") (pintype "passive"))
      (node (ref "U1") (pin "39") (pinfunction "VDDA_39") (pintype "passive"))
    )
    (net (code "169") (name "Net-(U1-VREF+)") (class "Default")
      (node (ref "C10") (pin "2") (pintype "passive"))
      (node (ref "C9") (pin "2") (pintype "passive"))
      (node (ref "R3") (pin "2") (pintype "passive"))
      (node (ref "U1") (pin "38") (pinfunction "VREF+_38") (pintype "passive"))
    )
    (net (code "170") (name "Net-(U2-AUXL)") (class "Default")
      (node (ref "C65") (pin "1") (pintype "passive"))
      (node (ref "U2") (pin "19") (pinfunction "AUXL_19") (pintype "passive"))
    )
    (net (code "171") (name "Net-(U2-AUXR)") (class "Default")
      (node (ref "C66") (pin "1") (pintype "passive"))
      (node (ref "U2") (pin "20") (pinfunction "AUXR_20") (pintype "passive"))
    )
    (net (code "172") (name "Net-(U2-DBVDD)") (class "Default")
      (node (ref "C57") (pin "2") (pintype "passive"))
      (node (ref "C58") (pin "2") (pintype "passive"))
      (node (ref "R30") (pin "2") (pintype "passive"))
      (node (ref "U2") (pin "13") (pinfunction "DCVDD_13") (pintype "passive"))
      (node (ref "U2") (pin "14") (pinfunction "DBVDD_14") (pintype "passive"))
    )
    (net (code "173") (name "Net-(U2-L2{slash}GPIO2)") (class "Default")
      (node (ref "C59") (pin "1") (pintype "passive"))
      (node (ref "U2") (pin "3") (pinfunction "L2/GPIO2_3") (pintype "passive"))
    )
    (net (code "174") (name "Net-(U2-LIN)") (class "Default")
      (node (ref "C62") (pin "1") (pintype "passive"))
      (node (ref "U2") (pin "2") (pinfunction "LIN_2") (pintype "passive"))
    )
    (net (code "175") (name "Net-(U2-LIP)") (class "Default")
      (node (ref "C61") (pin "1") (pintype "passive"))
      (node (ref "U2") (pin "1") (pinfunction "LIP_1") (pintype "passive"))
    )
    (net (code "176") (name "Net-(U2-LOUT2)") (class "Default")
      (node (ref "SPK+") (pin "1") (pinfunction "1_1") (pintype "passive"))
      (node (ref "U2") (pin "25") (pinfunction "LOUT2_25") (pintype "passive"))
    )
    (net (code "177") (name "Net-(U2-MICBIAS)") (class "Default")
      (node (ref "C68") (pin "2") (pintype "passive"))
      (node (ref "R33") (pin "1") (pintype "passive"))
      (node (ref "U2") (pin "32") (pinfunction "MICBIAS_32") (pintype "passive"))
    )
    (net (code "178") (name "Net-(U2-MODE)") (class "Default")
      (node (ref "R32") (pin "2") (pintype "passive"))
      (node (ref "U2") (pin "18") (pinfunction "MODE_18") (pintype "passive"))
    )
    (net (code "179") (name "Net-(U2-R2{slash}GPIO3)") (class "Default")
      (node (ref "C60") (pin "1") (pintype "passive"))
      (node (ref "U2") (pin "6") (pinfunction "R2/GPIO3_6") (pintype "passive"))
    )
    (net (code "180") (name "Net-(U2-RIN)") (class "Default")
      (node (ref "C64") (pin "1") (pintype "passive"))
      (node (ref "U2") (pin "5") (pinfunction "RIN_5") (pintype "passive"))
    )
    (net (code "181") (name "Net-(U2-RIP)") (class "Default")
      (node (ref "C63") (pin "1") (pintype "passive"))
      (node (ref "U2") (pin "4") (pinfunction "RIP_4") (pintype "passive"))
    )
    (net (code "182") (name "Net-(U2-ROUT2)") (class "Default")
      (node (ref "SPK-") (pin "1") (pinfunction "1_1") (pintype "passive"))
      (node (ref "U2") (pin "23") (pinfunction "ROUT2_23") (pintype "passive"))
    )
    (net (code "183") (name "Net-(U2-SPKVDD)") (class "Default")
      (node (ref "C55") (pin "2") (pintype "passive"))
      (node (ref "C56") (pin "2") (pintype "passive"))
      (node (ref "R29") (pin "1") (pintype "passive"))
      (node (ref "U2") (pin "26") (pinfunction "SPKVDD_26") (pintype "passive"))
    )
    (net (code "184") (name "Net-(U2-VMID)") (class "Default")
      (node (ref "C67") (pin "2") (pintype "passive"))
      (node (ref "U2") (pin "27") (pinfunction "VMID_27") (pintype "passive"))
    )
    (net (code "185") (name "Net-(U10-~{WP})") (class "Default")
      (node (ref "R21") (pin "1") (pintype "passive"))
      (node (ref "U10") (pin "19") (pinfunction "~{WP}_19") (pintype "passive"))
    )
    (net (code "186") (name "Net-(U14-D+)") (class "Default")
      (node (ref "U14") (pin "5") (pinfunction "D+_5") (pintype "passive"))
      (node (ref "USB_232") (pin "3") (pinfunction "D+_3") (pintype "passive"))
    )
    (net (code "187") (name "Net-(U14-D-)") (class "Default")
      (node (ref "U14") (pin "6") (pinfunction "D-_6") (pintype "passive"))
      (node (ref "USB_232") (pin "2") (pinfunction "D-_2") (pintype "passive"))
    )
    (net (code "188") (name "Net-(U14-V3)") (class "Default")
      (node (ref "C28") (pin "2") (pintype "passive"))
      (node (ref "U14") (pin "4") (pinfunction "V3_4") (pintype "passive"))
    )
    (net (code "189") (name "Net-(U14-XI)") (class "Default")
      (node (ref "C29") (pin "2") (pintype "passive"))
      (node (ref "U14") (pin "7") (pinfunction "XI_7") (pintype "passive"))
      (node (ref "Y3") (pin "1") (pinfunction "OSC1_1") (pintype "passive"))
    )
    (net (code "190") (name "Net-(U14-XO)") (class "Default")
      (node (ref "C30") (pin "1") (pintype "passive"))
      (node (ref "U14") (pin "8") (pinfunction "XO_8") (pintype "passive"))
      (node (ref "Y3") (pin "2") (pinfunction "OSC2_2") (pintype "passive"))
    )
    (net (code "191") (name "Net-(USB_SLAVE-D+)") (class "Default")
      (node (ref "R13") (pin "1") (pintype "passive"))
      (node (ref "R14") (pin "1") (pintype "passive"))
      (node (ref "USB_SLAVE") (pin "3") (pinfunction "D+_3") (pintype "passive"))
    )
    (net (code "192") (name "Net-(USB_SLAVE-D-)") (class "Default")
      (node (ref "R12") (pin "1") (pintype "passive"))
      (node (ref "USB_SLAVE") (pin "2") (pinfunction "D-_2") (pintype "passive"))
    )
    (net (code "193") (name "VCC3.3") (class "Default")
      (node (ref "C13") (pin "2") (pintype "passive"))
      (node (ref "C14") (pin "2") (pintype "passive"))
      (node (ref "C15") (pin "2") (pintype "passive"))
      (node (ref "C16") (pin "2") (pintype "passive"))
      (node (ref "C17") (pin "2") (pintype "passive"))
      (node (ref "C18") (pin "2") (pintype "passive"))
      (node (ref "C19") (pin "2") (pintype "passive"))
      (node (ref "C20") (pin "2") (pintype "passive"))
      (node (ref "C21") (pin "2") (pintype "passive"))
      (node (ref "C22") (pin "2") (pintype "passive"))
      (node (ref "C23") (pin "2") (pintype "passive"))
      (node (ref "C24") (pin "2") (pintype "passive"))
      (node (ref "C25") (pin "2") (pintype "passive"))
      (node (ref "C26") (pin "2") (pintype "passive"))
      (node (ref "C27") (pin "2") (pintype "passive"))
      (node (ref "C34") (pin "2") (pintype "passive"))
      (node (ref "C35") (pin "1") (pinfunction "VCC_1") (pintype "passive"))
      (node (ref "C36") (pin "1") (pintype "passive"))
      (node (ref "C38") (pin "1") (pintype "passive"))
      (node (ref "C39") (pin "1") (pintype "passive"))
      (node (ref "C42") (pin "2") (pintype "passive"))
      (node (ref "C43") (pin "2") (pintype "passive"))
      (node (ref "C44") (pin "2") (pintype "passive"))
      (node (ref "C45") (pin "2") (pintype "passive"))
      (node (ref "C46") (pin "2") (pintype "passive"))
      (node (ref "C47") (pin "2") (pintype "passive"))
      (node (ref "C48") (pin "2") (pintype "passive"))
      (node (ref "C49") (pin "1") (pintype "passive"))
      (node (ref "C51") (pin "1") (pintype "passive"))
      (node (ref "C52") (pin "1") (pintype "passive"))
      (node (ref "C69") (pin "2") (pintype "passive"))
      (node (ref "D1") (pin "1") (pintype "passive"))
      (node (ref "LCD1") (pin "24") (pinfunction "VDD3.3_24") (pintype "passive"))
      (node (ref "LCD1") (pin "25") (pinfunction "VDD3.3_25") (pintype "passive"))
      (node (ref "R10") (pin "2") (pintype "passive"))
      (node (ref "R11") (pin "2") (pintype "passive"))
      (node (ref "R13") (pin "2") (pintype "passive"))
      (node (ref "R15") (pin "2") (pintype "passive"))
      (node (ref "R16") (pin "2") (pintype "passive"))
      (node (ref "R17") (pin "2") (pintype "passive"))
      (node (ref "R18") (pin "2") (pintype "passive"))
      (node (ref "R19") (pin "2") (pintype "passive"))
      (node (ref "R2") (pin "1") (pintype "passive"))
      (node (ref "R20") (pin "2") (pintype "passive"))
      (node (ref "R21") (pin "2") (pintype "passive"))
      (node (ref "R22") (pin "1") (pintype "passive"))
      (node (ref "R36") (pin "1") (pintype "passive"))
      (node (ref "R37") (pin "2") (pintype "passive"))
      (node (ref "R38") (pin "2") (pintype "passive"))
      (node (ref "R39") (pin "2") (pintype "passive"))
      (node (ref "R4") (pin "2") (pintype "passive"))
      (node (ref "R40") (pin "2") (pintype "passive"))
      (node (ref "R5") (pin "2") (pintype "passive"))
      (node (ref "TF_CARD") (pin "4") (pinfunction "VDD_4") (pintype "passive"))
      (node (ref "U1") (pin "103") (pinfunction "VDD_103") (pintype "passive"))
      (node (ref "U1") (pin "114") (pinfunction "VDD_114") (pintype "passive"))
      (node (ref "U1") (pin "127") (pinfunction "VDD_127") (pintype "passive"))
      (node (ref "U1") (pin "136") (pinfunction "VDD_136") (pintype "passive"))
      (node (ref "U1") (pin "149") (pinfunction "VDD_149") (pintype "passive"))
      (node (ref "U1") (pin "15") (pinfunction "VDD_15") (pintype "passive"))
      (node (ref "U1") (pin "159") (pinfunction "VDD_159") (pintype "passive"))
      (node (ref "U1") (pin "172") (pinfunction "VDD_172") (pintype "passive"))
      (node (ref "U1") (pin "23") (pinfunction "VDD_23") (pintype "passive"))
      (node (ref "U1") (pin "36") (pinfunction "VDD_36") (pintype "passive"))
      (node (ref "U1") (pin "49") (pinfunction "VDD_49") (pintype "passive"))
      (node (ref "U1") (pin "62") (pinfunction "VDD_62") (pintype "passive"))
      (node (ref "U1") (pin "72") (pinfunction "VDD_72") (pintype "passive"))
      (node (ref "U1") (pin "82") (pinfunction "VDD_82") (pintype "passive"))
      (node (ref "U1") (pin "91") (pinfunction "VDD_91") (pintype "passive"))
      (node (ref "U11") (pin "1") (pinfunction "VDD0_1") (pintype "power_in"))
      (node (ref "U11") (pin "14") (pinfunction "VDD1_14") (pintype "power_in"))
      (node (ref "U11") (pin "27") (pinfunction "VDD2_27") (pintype "power_in"))
      (node (ref "U11") (pin "3") (pinfunction "VDDQ0_3") (pintype "power_in"))
      (node (ref "U11") (pin "43") (pinfunction "VDDQ2_43") (pintype "power_in"))
      (node (ref "U11") (pin "49") (pinfunction "VDDQ3_49") (pintype "power_in"))
      (node (ref "U11") (pin "9") (pinfunction "VDDQ1_9") (pintype "power_in"))
      (node (ref "U12") (pin "2") (pinfunction "OUT_2") (pintype "passive"))
      (node (ref "U12") (pin "4") (pinfunction "OUT_4") (pintype "passive"))
      (node (ref "U2") (pin "31") (pinfunction "AVDD_31") (pintype "passive"))
      (node (ref "U3") (pin "8") (pinfunction "VCC1_8") (pintype "passive"))
      (node (ref "U4") (pin "8") (pinfunction "VCC_8") (pintype "passive"))
      (node (ref "U6") (pin "1") (pinfunction "VCC_1") (pintype "passive"))
    )
    (net (code "194") (name "VCC5") (class "Default")
      (node (ref "C31") (pin "1") (pintype "passive"))
      (node (ref "C32") (pin "1") (pintype "passive"))
      (node (ref "C33") (pin "2") (pintype "passive"))
      (node (ref "C50") (pin "2") (pintype "passive"))
      (node (ref "J1") (pin "1") (pinfunction "1_1") (pintype "passive"))
      (node (ref "J1") (pin "2") (pinfunction "2_2") (pintype "passive"))
      (node (ref "LCD1") (pin "28") (pinfunction "BL_VDD_28") (pintype "passive"))
      (node (ref "POWER") (pin "1") (pinfunction "I/O_1") (pintype "passive"))
      (node (ref "R29") (pin "2") (pintype "passive"))
      (node (ref "U12") (pin "3") (pinfunction "IN_3") (pintype "passive"))
      (node (ref "U14") (pin "16") (pinfunction "VCC_16") (pintype "passive"))
    )
    (net (code "195") (name "unconnected-(J1-PadA)") (class "Default")
      (node (ref "J1") (pin "A") (pinfunction "A_A") (pintype "passive"))
    )
    (net (code "196") (name "unconnected-(J1-PadB)") (class "Default")
      (node (ref "J1") (pin "B") (pinfunction "B_B") (pintype "passive"))
    )
    (net (code "197") (name "unconnected-(LCD1-MO-Pad32)") (class "Default")
      (node (ref "LCD1") (pin "32") (pinfunction "MO_32") (pintype "passive"))
    )
    (net (code "198") (name "unconnected-(POWER-GND-Pad4)") (class "Default")
      (node (ref "POWER") (pin "4") (pinfunction "GND_4") (pintype "passive"))
    )
    (net (code "199") (name "unconnected-(POWER-GND-Pad5)") (class "Default")
      (node (ref "POWER") (pin "5") (pinfunction "GND_5") (pintype "passive"))
    )
    (net (code "200") (name "unconnected-(POWER-I{slash}O-Pad3)") (class "Default")
      (node (ref "POWER") (pin "3") (pinfunction "I/O_3") (pintype "passive"))
    )
    (net (code "201") (name "unconnected-(R30-Pad1)") (class "Default")
      (node (ref "R30") (pin "1") (pintype "passive"))
    )
    (net (code "202") (name "unconnected-(U2-CSB{slash}GPIO1-Pad15)") (class "Default")
      (node (ref "U2") (pin "15") (pinfunction "CSB/GPIO1_15") (pintype "passive"))
    )
    (net (code "203") (name "unconnected-(U2-OUT3-Pad22)") (class "Default")
      (node (ref "U2") (pin "22") (pinfunction "OUT3_22") (pintype "passive"))
    )
    (net (code "204") (name "unconnected-(U2-OUT4-Pad21)") (class "Default")
      (node (ref "U2") (pin "21") (pinfunction "OUT4_21") (pintype "passive"))
    )
    (net (code "205") (name "unconnected-(U14-CTS#-Pad9)") (class "Default")
      (node (ref "U14") (pin "9") (pinfunction "CTS#_9") (pintype "passive"))
    )
    (net (code "206") (name "unconnected-(U14-DCD#-Pad12)") (class "Default")
      (node (ref "U14") (pin "12") (pinfunction "DCD#_12") (pintype "passive"))
    )
    (net (code "207") (name "unconnected-(U14-DSR#-Pad10)") (class "Default")
      (node (ref "U14") (pin "10") (pinfunction "DSR#_10") (pintype "passive"))
    )
    (net (code "208") (name "unconnected-(U14-DTR#-Pad13)") (class "Default")
      (node (ref "U14") (pin "13") (pinfunction "DTR#_13") (pintype "passive"))
    )
    (net (code "209") (name "unconnected-(U14-R232-Pad15)") (class "Default")
      (node (ref "U14") (pin "15") (pinfunction "R232_15") (pintype "passive"))
    )
    (net (code "210") (name "unconnected-(U14-RI#-Pad11)") (class "Default")
      (node (ref "U14") (pin "11") (pinfunction "RI#_11") (pintype "passive"))
    )
    (net (code "211") (name "unconnected-(U14-RTS#-Pad14)") (class "Default")
      (node (ref "U14") (pin "14") (pinfunction "RTS#_14") (pintype "passive"))
    )
    (net (code "212") (name "unconnected-(USB_232-NC-Pad4)") (class "Default")
      (node (ref "USB_232") (pin "4") (pinfunction "NC_4") (pintype "passive"))
    )
    (net (code "213") (name "unconnected-(USB_SLAVE-NC-Pad4)") (class "Default")
      (node (ref "USB_SLAVE") (pin "4") (pinfunction "NC_4") (pintype "passive"))
    )
  )
)
